# EEG_ECG.net
KiCad netlist of a schematic drawn in Altium Designer
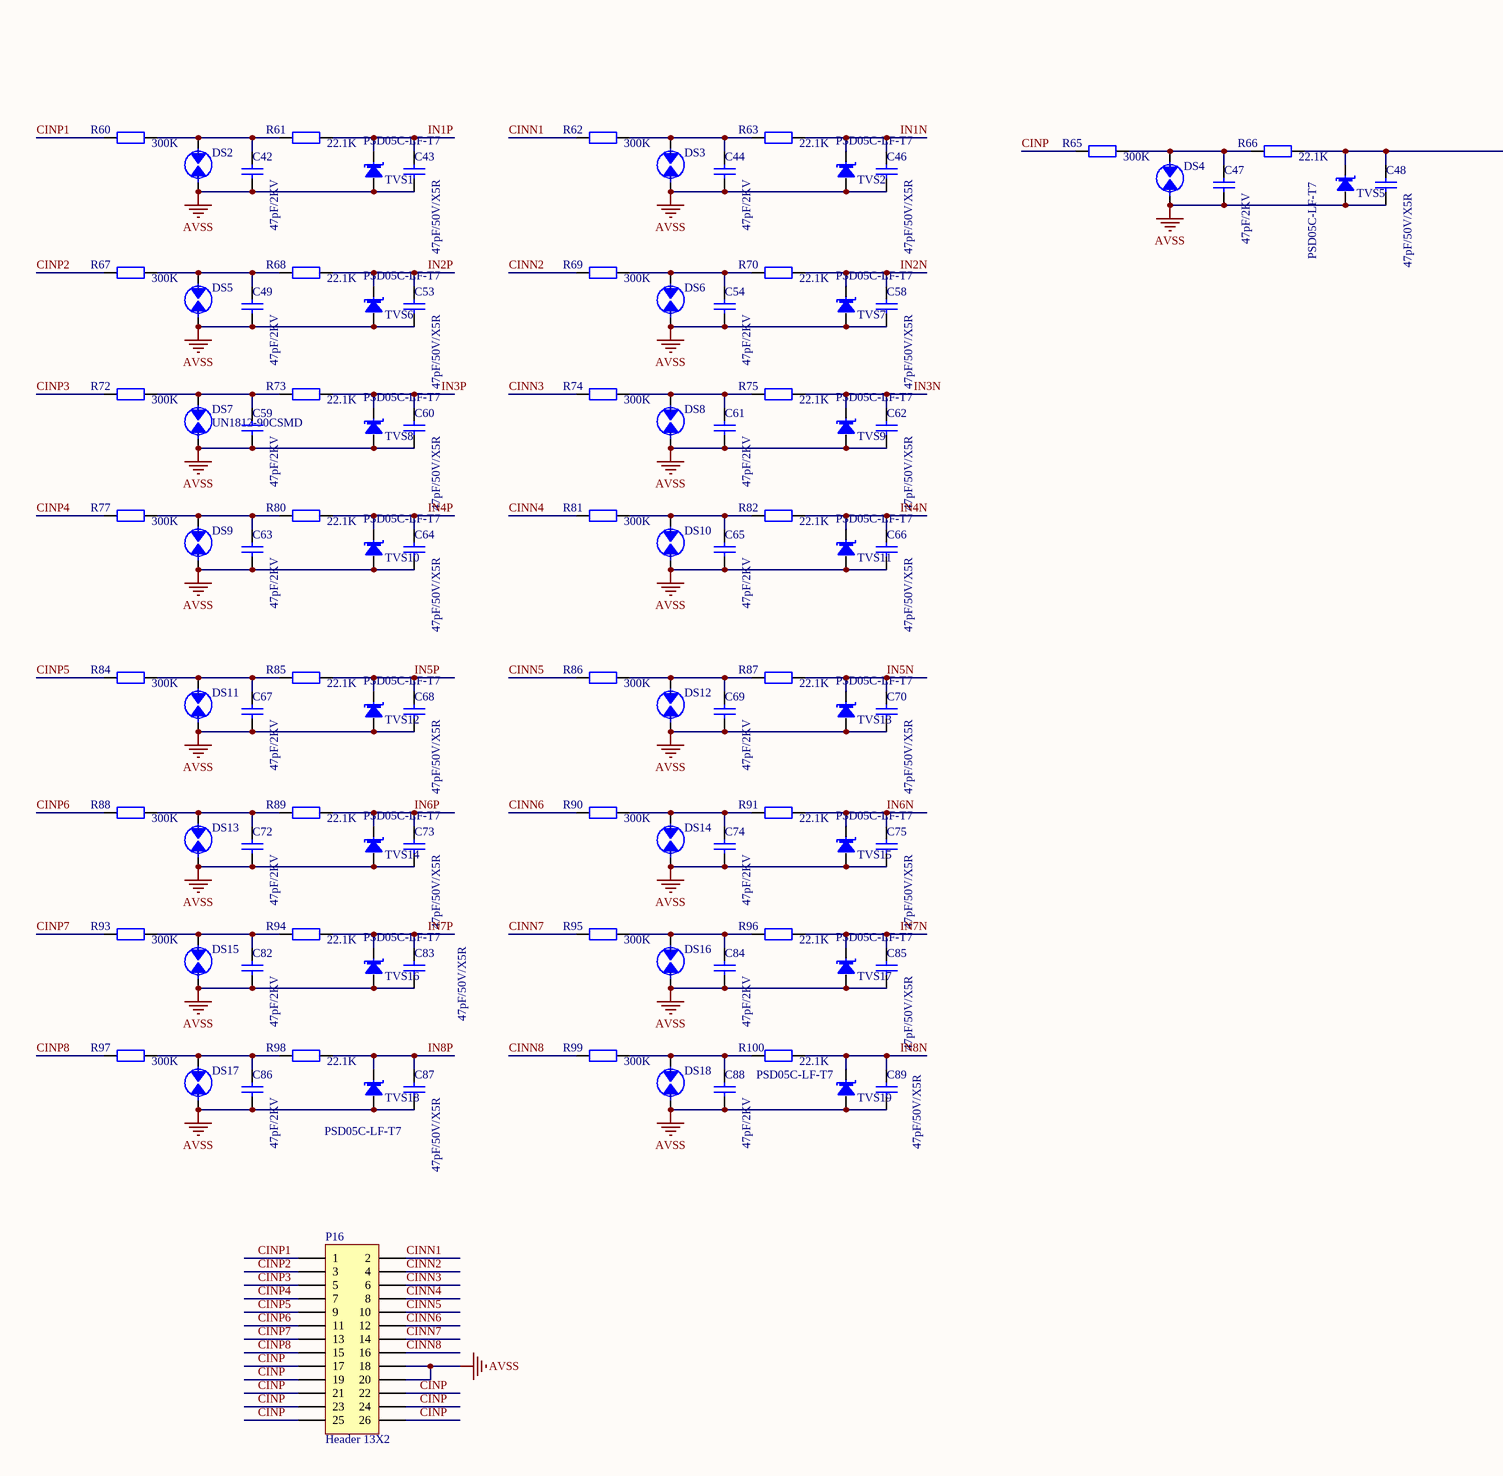
[diagram p0: EEG&ECG.SchDoc, top left]
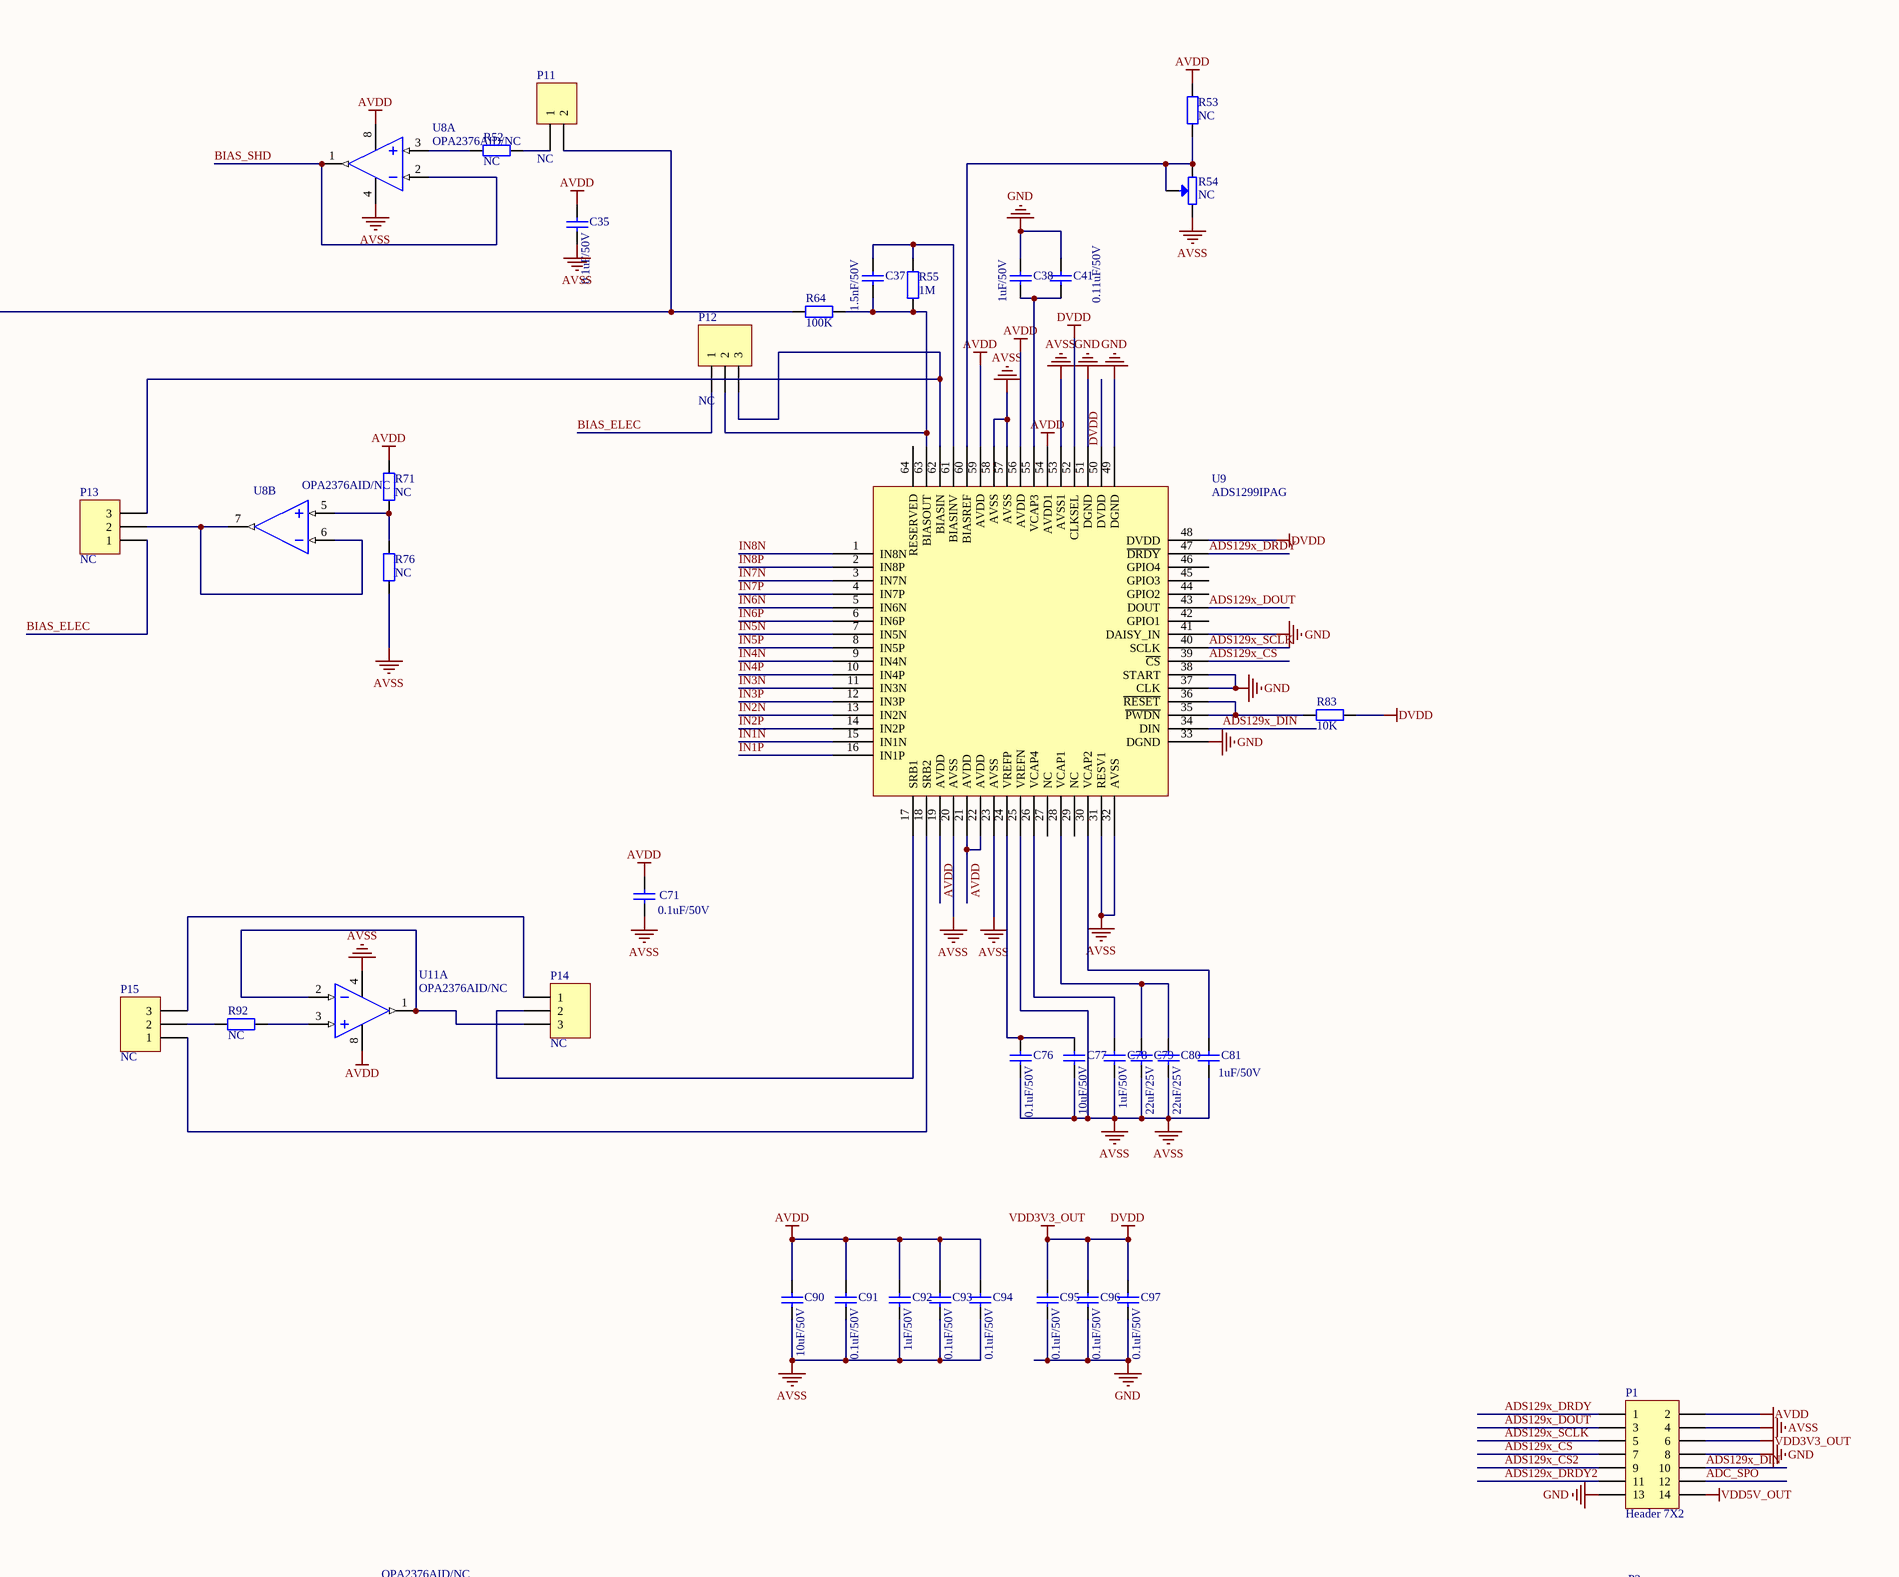
[diagram p1: EEG&ECG.SchDoc, top right]
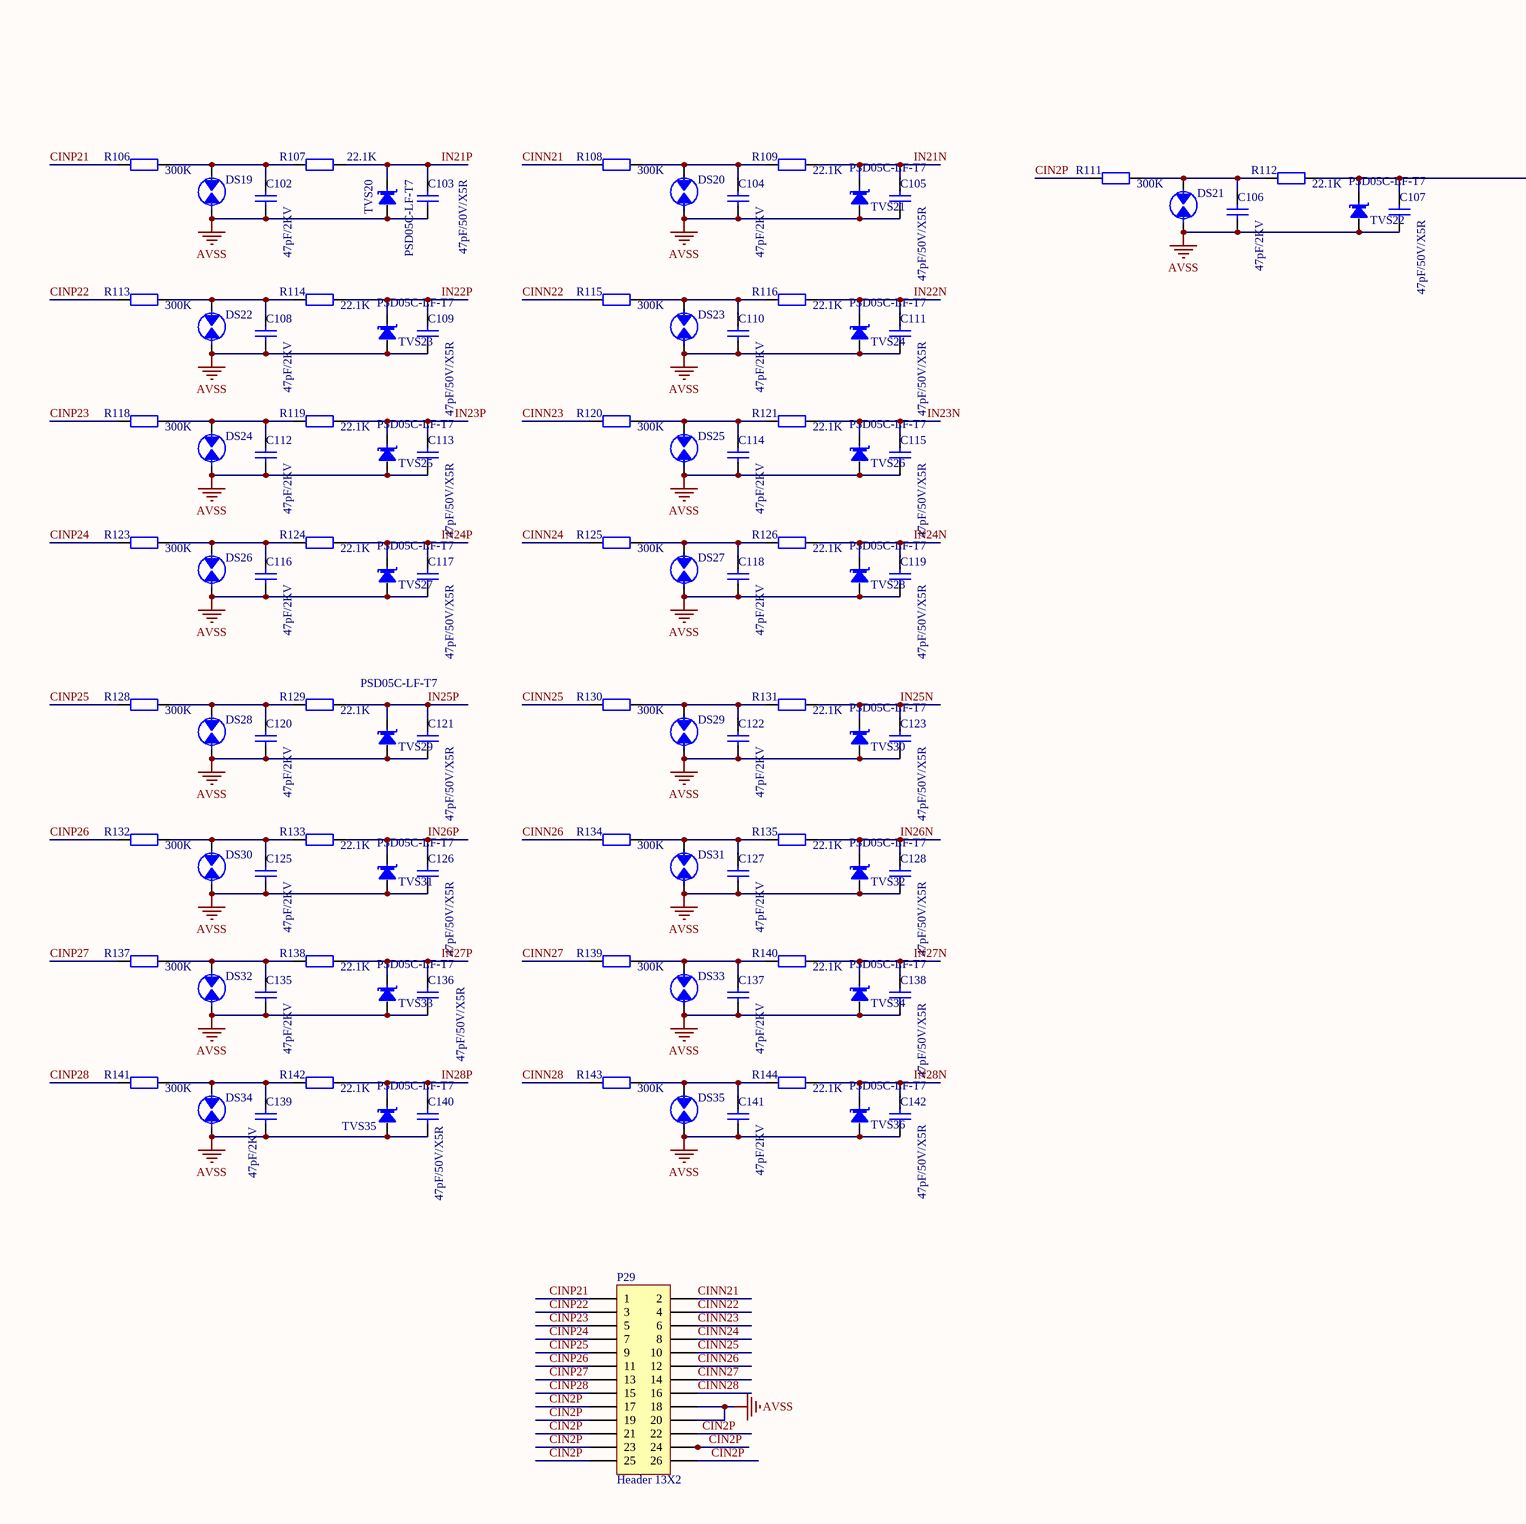
[diagram p2: EEG&ECG.SchDoc, bottom left]
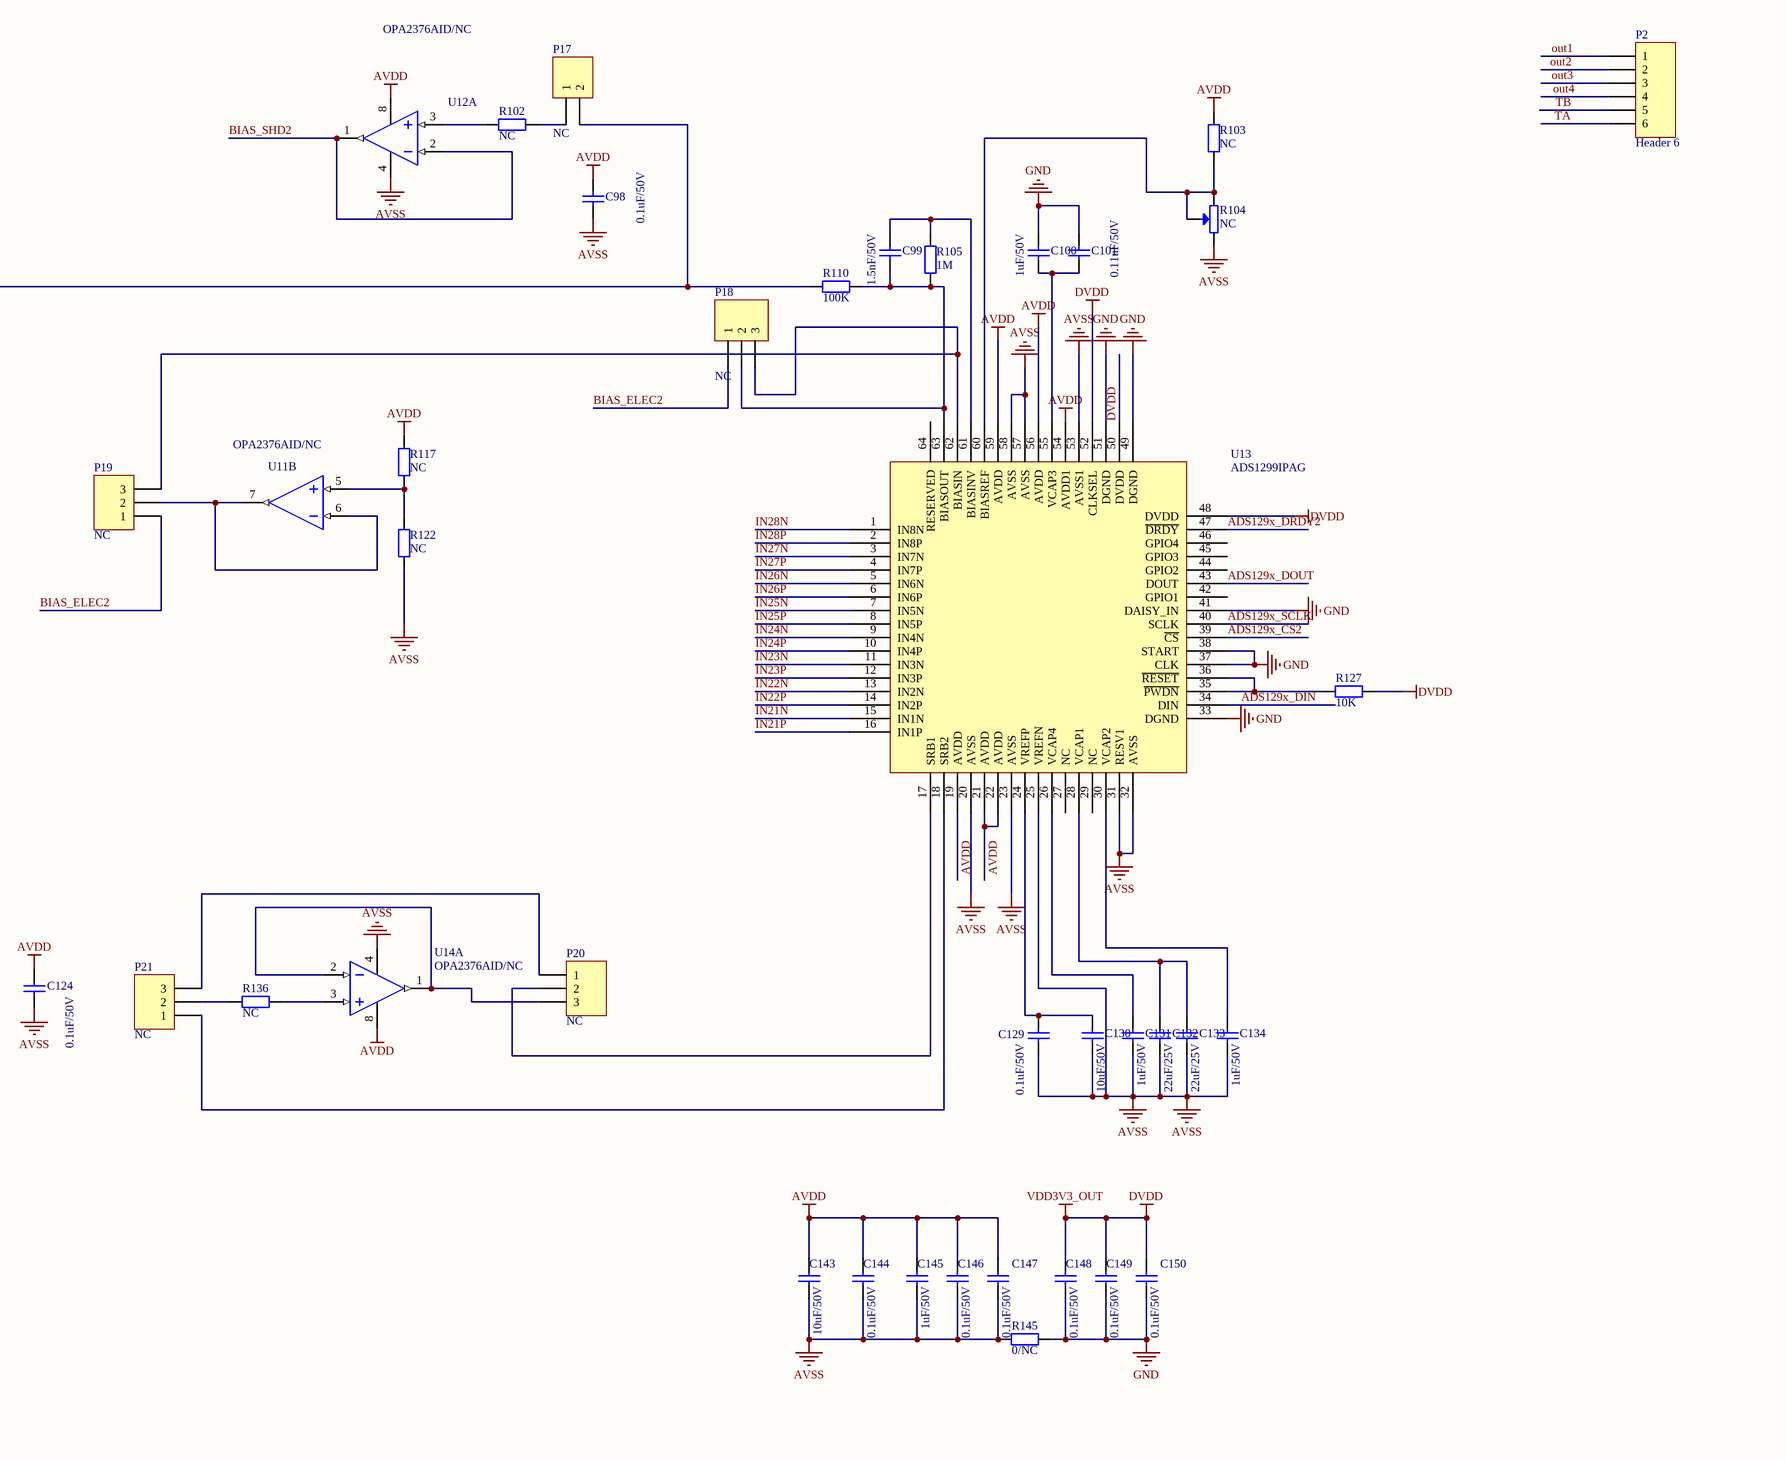
[diagram p3: EEG&ECG.SchDoc, bottom right]

(export (version "E")
  (design (tool "Eeschema 10.0.6"))
  (components
    (comp (ref "C35")
      (value "0.1uF/50V")
      (footprint "SMD-0603C")
      (description "贴片电容 20%")
      (libsource (lib "XiaoyI") (part "CAP4"))
    )
    (comp (ref "C37")
      (value "1.5nF/50V")
      (footprint "SMD-0603C")
      (description "贴片电容 20%")
      (libsource (lib "XiaoyI") (part "CAP4"))
    )
    (comp (ref "C38")
      (value "1uF/50V")
      (footprint "SMD-0603C")
      (description "贴片电容 20%")
      (libsource (lib "XiaoyI") (part "CAP4"))
    )
    (comp (ref "C41")
      (value "0.11uF/50V")
      (footprint "SMD-0603C")
      (description "贴片电容 20%")
      (libsource (lib "XiaoyI") (part "CAP4"))
    )
    (comp (ref "C42")
      (value "47pF/2KV")
      (footprint "1206c")
      (description "贴片电容 10%")
      (libsource (lib "XiaoyI") (part "CAP4"))
    )
    (comp (ref "C43")
      (value "47pF/50V/X5R")
      (footprint "SMD-0603C")
      (description "贴片电容 10%")
      (libsource (lib "XiaoyI") (part "CAP4"))
    )
    (comp (ref "C44")
      (value "47pF/2KV")
      (footprint "1206c")
      (description "贴片电容 10%")
      (libsource (lib "XiaoyI") (part "CAP4"))
    )
    (comp (ref "C46")
      (value "47pF/50V/X5R")
      (footprint "SMD-0603C")
      (description "贴片电容 10%")
      (libsource (lib "XiaoyI") (part "CAP4"))
    )
    (comp (ref "C47")
      (value "47pF/2KV")
      (footprint "1206c")
      (description "贴片电容 10%")
      (libsource (lib "XiaoyI") (part "CAP4"))
    )
    (comp (ref "C48")
      (value "47pF/50V/X5R")
      (footprint "SMD-0603C")
      (description "贴片电容 10%")
      (libsource (lib "XiaoyI") (part "CAP4"))
    )
    (comp (ref "C49")
      (value "47pF/2KV")
      (footprint "1206c")
      (description "贴片电容 10%")
      (libsource (lib "XiaoyI") (part "CAP4"))
    )
    (comp (ref "C53")
      (value "47pF/50V/X5R")
      (footprint "SMD-0603C")
      (description "贴片电容 10%")
      (libsource (lib "XiaoyI") (part "CAP4"))
    )
    (comp (ref "C54")
      (value "47pF/2KV")
      (footprint "1206c")
      (description "贴片电容 10%")
      (libsource (lib "XiaoyI") (part "CAP4"))
    )
    (comp (ref "C58")
      (value "47pF/50V/X5R")
      (footprint "SMD-0603C")
      (description "贴片电容 10%")
      (libsource (lib "XiaoyI") (part "CAP4"))
    )
    (comp (ref "C59")
      (value "47pF/2KV")
      (footprint "1206c")
      (description "贴片电容 10%")
      (libsource (lib "XiaoyI") (part "CAP4"))
    )
    (comp (ref "C60")
      (value "47pF/50V/X5R")
      (footprint "SMD-0603C")
      (description "贴片电容 10%")
      (libsource (lib "XiaoyI") (part "CAP4"))
    )
    (comp (ref "C61")
      (value "47pF/2KV")
      (footprint "1206c")
      (description "贴片电容 10%")
      (libsource (lib "XiaoyI") (part "CAP4"))
    )
    (comp (ref "C62")
      (value "47pF/50V/X5R")
      (footprint "SMD-0603C")
      (description "贴片电容 10%")
      (libsource (lib "XiaoyI") (part "CAP4"))
    )
    (comp (ref "C63")
      (value "47pF/2KV")
      (footprint "1206c")
      (description "贴片电容 10%")
      (libsource (lib "XiaoyI") (part "CAP4"))
    )
    (comp (ref "C64")
      (value "47pF/50V/X5R")
      (footprint "SMD-0603C")
      (description "贴片电容 10%")
      (libsource (lib "XiaoyI") (part "CAP4"))
    )
    (comp (ref "C65")
      (value "47pF/2KV")
      (footprint "1206c")
      (description "贴片电容 10%")
      (libsource (lib "XiaoyI") (part "CAP4"))
    )
    (comp (ref "C66")
      (value "47pF/50V/X5R")
      (footprint "SMD-0603C")
      (description "贴片电容 10%")
      (libsource (lib "XiaoyI") (part "CAP4"))
    )
    (comp (ref "C67")
      (value "47pF/2KV")
      (footprint "1206c")
      (description "贴片电容 10%")
      (libsource (lib "XiaoyI") (part "CAP4"))
    )
    (comp (ref "C68")
      (value "47pF/50V/X5R")
      (footprint "SMD-0603C")
      (description "贴片电容 10%")
      (libsource (lib "XiaoyI") (part "CAP4"))
    )
    (comp (ref "C69")
      (value "47pF/2KV")
      (footprint "1206c")
      (description "贴片电容 10%")
      (libsource (lib "XiaoyI") (part "CAP4"))
    )
    (comp (ref "C70")
      (value "47pF/50V/X5R")
      (footprint "SMD-0603C")
      (description "贴片电容 10%")
      (libsource (lib "XiaoyI") (part "CAP4"))
    )
    (comp (ref "C71")
      (value "0.1uF/50V")
      (footprint "SMD-0603C")
      (description "贴片电容 20%")
      (libsource (lib "XiaoyI") (part "CAP4"))
    )
    (comp (ref "C72")
      (value "47pF/2KV")
      (footprint "1206c")
      (description "贴片电容 10%")
      (libsource (lib "XiaoyI") (part "CAP4"))
    )
    (comp (ref "C73")
      (value "47pF/50V/X5R")
      (footprint "SMD-0603C")
      (description "贴片电容 10%")
      (libsource (lib "XiaoyI") (part "CAP4"))
    )
    (comp (ref "C74")
      (value "47pF/2KV")
      (footprint "1206c")
      (description "贴片电容 10%")
      (libsource (lib "XiaoyI") (part "CAP4"))
    )
    (comp (ref "C75")
      (value "47pF/50V/X5R")
      (footprint "SMD-0603C")
      (description "贴片电容 10%")
      (libsource (lib "XiaoyI") (part "CAP4"))
    )
    (comp (ref "C76")
      (value "0.1uF/50V")
      (footprint "SMD-0603C")
      (description "贴片电容 20%")
      (libsource (lib "XiaoyI") (part "CAP4"))
    )
    (comp (ref "C77")
      (value "10uF/50V")
      (footprint "SMD-0805C")
      (description "贴片电容 20%")
      (libsource (lib "XiaoyI") (part "CAP4"))
    )
    (comp (ref "C78")
      (value "1uF/50V")
      (footprint "SMD-0603C")
      (description "贴片电容 20%")
      (libsource (lib "XiaoyI") (part "CAP4"))
    )
    (comp (ref "C79")
      (value "22uF/25V")
      (footprint "SMD-0805C")
      (description "贴片电容 20%")
      (libsource (lib "XiaoyI") (part "CAP4"))
    )
    (comp (ref "C80")
      (value "22uF/25V")
      (footprint "SMD-0805C")
      (description "贴片电容 20%")
      (libsource (lib "XiaoyI") (part "CAP4"))
    )
    (comp (ref "C81")
      (value "1uF/50V")
      (footprint "SMD-0603C")
      (description "贴片电容 20%")
      (libsource (lib "XiaoyI") (part "CAP4"))
    )
    (comp (ref "C82")
      (value "47pF/2KV")
      (footprint "1206c")
      (description "贴片电容 10%")
      (libsource (lib "XiaoyI") (part "CAP4"))
    )
    (comp (ref "C83")
      (value "47pF/50V/X5R")
      (footprint "SMD-0603C")
      (description "贴片电容 10%")
      (libsource (lib "XiaoyI") (part "CAP4"))
    )
    (comp (ref "C84")
      (value "47pF/2KV")
      (footprint "1206c")
      (description "贴片电容 10%")
      (libsource (lib "XiaoyI") (part "CAP4"))
    )
    (comp (ref "C85")
      (value "47pF/50V/X5R")
      (footprint "SMD-0603C")
      (description "贴片电容 10%")
      (libsource (lib "XiaoyI") (part "CAP4"))
    )
    (comp (ref "C86")
      (value "47pF/2KV")
      (footprint "1206c")
      (description "贴片电容 10%")
      (libsource (lib "XiaoyI") (part "CAP4"))
    )
    (comp (ref "C87")
      (value "47pF/50V/X5R")
      (footprint "SMD-0603C")
      (description "贴片电容 10%")
      (libsource (lib "XiaoyI") (part "CAP4"))
    )
    (comp (ref "C88")
      (value "47pF/2KV")
      (footprint "1206c")
      (description "贴片电容 10%")
      (libsource (lib "XiaoyI") (part "CAP4"))
    )
    (comp (ref "C89")
      (value "47pF/50V/X5R")
      (footprint "SMD-0603C")
      (description "贴片电容 10%")
      (libsource (lib "XiaoyI") (part "CAP4"))
    )
    (comp (ref "C90")
      (value "10uF/50V")
      (footprint "SMD-0805C")
      (description "贴片电容 20%")
      (libsource (lib "XiaoyI") (part "CAP4"))
    )
    (comp (ref "C91")
      (value "0.1uF/50V")
      (footprint "SMD-0603C")
      (description "贴片电容 20%")
      (libsource (lib "XiaoyI") (part "CAP4"))
    )
    (comp (ref "C92")
      (value "1uF/50V")
      (footprint "SMD-0603C")
      (description "贴片电容 20%")
      (libsource (lib "XiaoyI") (part "CAP4"))
    )
    (comp (ref "C93")
      (value "0.1uF/50V")
      (footprint "SMD-0603C")
      (description "贴片电容 20%")
      (libsource (lib "XiaoyI") (part "CAP4"))
    )
    (comp (ref "C94")
      (value "0.1uF/50V")
      (footprint "SMD-0603C")
      (description "贴片电容 20%")
      (libsource (lib "XiaoyI") (part "CAP4"))
    )
    (comp (ref "C95")
      (value "0.1uF/50V")
      (footprint "SMD-0603C")
      (description "贴片电容 20%")
      (libsource (lib "XiaoyI") (part "CAP4"))
    )
    (comp (ref "C96")
      (value "0.1uF/50V")
      (footprint "SMD-0603C")
      (description "贴片电容 20%")
      (libsource (lib "XiaoyI") (part "CAP4"))
    )
    (comp (ref "C97")
      (value "0.1uF/50V")
      (footprint "SMD-0603C")
      (description "贴片电容 20%")
      (libsource (lib "XiaoyI") (part "CAP4"))
    )
    (comp (ref "C98")
      (value "0.1uF/50V")
      (footprint "SMD-0603C")
      (description "贴片电容 20%")
      (libsource (lib "XiaoyI") (part "CAP4"))
    )
    (comp (ref "C99")
      (value "1.5nF/50V")
      (footprint "SMD-0603C")
      (description "贴片电容 20%")
      (libsource (lib "XiaoyI") (part "CAP4"))
    )
    (comp (ref "C100")
      (value "1uF/50V")
      (footprint "SMD-0603C")
      (description "贴片电容 20%")
      (libsource (lib "XiaoyI") (part "CAP4"))
    )
    (comp (ref "C101")
      (value "0.11uF/50V")
      (footprint "SMD-0603C")
      (description "贴片电容 20%")
      (libsource (lib "XiaoyI") (part "CAP4"))
    )
    (comp (ref "C102")
      (value "47pF/2KV")
      (footprint "1206c")
      (description "贴片电容 10%")
      (libsource (lib "XiaoyI") (part "CAP4"))
    )
    (comp (ref "C103")
      (value "47pF/50V/X5R")
      (footprint "SMD-0603C")
      (description "贴片电容 10%")
      (libsource (lib "XiaoyI") (part "CAP4"))
    )
    (comp (ref "C104")
      (value "47pF/2KV")
      (footprint "1206c")
      (description "贴片电容 10%")
      (libsource (lib "XiaoyI") (part "CAP4"))
    )
    (comp (ref "C105")
      (value "47pF/50V/X5R")
      (footprint "SMD-0603C")
      (description "贴片电容 10%")
      (libsource (lib "XiaoyI") (part "CAP4"))
    )
    (comp (ref "C106")
      (value "47pF/2KV")
      (footprint "1206c")
      (description "贴片电容 10%")
      (libsource (lib "XiaoyI") (part "CAP4"))
    )
    (comp (ref "C107")
      (value "47pF/50V/X5R")
      (footprint "SMD-0603C")
      (description "贴片电容 10%")
      (libsource (lib "XiaoyI") (part "CAP4"))
    )
    (comp (ref "C108")
      (value "47pF/2KV")
      (footprint "1206c")
      (description "贴片电容 10%")
      (libsource (lib "XiaoyI") (part "CAP4"))
    )
    (comp (ref "C109")
      (value "47pF/50V/X5R")
      (footprint "SMD-0603C")
      (description "贴片电容 10%")
      (libsource (lib "XiaoyI") (part "CAP4"))
    )
    (comp (ref "C110")
      (value "47pF/2KV")
      (footprint "1206c")
      (description "贴片电容 10%")
      (libsource (lib "XiaoyI") (part "CAP4"))
    )
    (comp (ref "C111")
      (value "47pF/50V/X5R")
      (footprint "SMD-0603C")
      (description "贴片电容 10%")
      (libsource (lib "XiaoyI") (part "CAP4"))
    )
    (comp (ref "C112")
      (value "47pF/2KV")
      (footprint "1206c")
      (description "贴片电容 10%")
      (libsource (lib "XiaoyI") (part "CAP4"))
    )
    (comp (ref "C113")
      (value "47pF/50V/X5R")
      (footprint "SMD-0603C")
      (description "贴片电容 10%")
      (libsource (lib "XiaoyI") (part "CAP4"))
    )
    (comp (ref "C114")
      (value "47pF/2KV")
      (footprint "1206c")
      (description "贴片电容 10%")
      (libsource (lib "XiaoyI") (part "CAP4"))
    )
    (comp (ref "C115")
      (value "47pF/50V/X5R")
      (footprint "SMD-0603C")
      (description "贴片电容 10%")
      (libsource (lib "XiaoyI") (part "CAP4"))
    )
    (comp (ref "C116")
      (value "47pF/2KV")
      (footprint "1206c")
      (description "贴片电容 10%")
      (libsource (lib "XiaoyI") (part "CAP4"))
    )
    (comp (ref "C117")
      (value "47pF/50V/X5R")
      (footprint "SMD-0603C")
      (description "贴片电容 10%")
      (libsource (lib "XiaoyI") (part "CAP4"))
    )
    (comp (ref "C118")
      (value "47pF/2KV")
      (footprint "1206c")
      (description "贴片电容 10%")
      (libsource (lib "XiaoyI") (part "CAP4"))
    )
    (comp (ref "C119")
      (value "47pF/50V/X5R")
      (footprint "SMD-0603C")
      (description "贴片电容 10%")
      (libsource (lib "XiaoyI") (part "CAP4"))
    )
    (comp (ref "C120")
      (value "47pF/2KV")
      (footprint "1206c")
      (description "贴片电容 10%")
      (libsource (lib "XiaoyI") (part "CAP4"))
    )
    (comp (ref "C121")
      (value "47pF/50V/X5R")
      (footprint "SMD-0603C")
      (description "贴片电容 10%")
      (libsource (lib "XiaoyI") (part "CAP4"))
    )
    (comp (ref "C122")
      (value "47pF/2KV")
      (footprint "1206c")
      (description "贴片电容 10%")
      (libsource (lib "XiaoyI") (part "CAP4"))
    )
    (comp (ref "C123")
      (value "47pF/50V/X5R")
      (footprint "SMD-0603C")
      (description "贴片电容 10%")
      (libsource (lib "XiaoyI") (part "CAP4"))
    )
    (comp (ref "C124")
      (value "0.1uF/50V")
      (footprint "SMD-0603C")
      (description "贴片电容 20%")
      (libsource (lib "XiaoyI") (part "CAP4"))
    )
    (comp (ref "C125")
      (value "47pF/2KV")
      (footprint "1206c")
      (description "贴片电容 10%")
      (libsource (lib "XiaoyI") (part "CAP4"))
    )
    (comp (ref "C126")
      (value "47pF/50V/X5R")
      (footprint "SMD-0603C")
      (description "贴片电容 10%")
      (libsource (lib "XiaoyI") (part "CAP4"))
    )
    (comp (ref "C127")
      (value "47pF/2KV")
      (footprint "1206c")
      (description "贴片电容 10%")
      (libsource (lib "XiaoyI") (part "CAP4"))
    )
    (comp (ref "C128")
      (value "47pF/50V/X5R")
      (footprint "SMD-0603C")
      (description "贴片电容 10%")
      (libsource (lib "XiaoyI") (part "CAP4"))
    )
    (comp (ref "C129")
      (value "0.1uF/50V")
      (footprint "SMD-0603C")
      (description "贴片电容 20%")
      (libsource (lib "XiaoyI") (part "CAP4"))
    )
    (comp (ref "C130")
      (value "10uF/50V")
      (footprint "SMD-0805C")
      (description "贴片电容 20%")
      (libsource (lib "XiaoyI") (part "CAP4"))
    )
    (comp (ref "C131")
      (value "1uF/50V")
      (footprint "SMD-0603C")
      (description "贴片电容 20%")
      (libsource (lib "XiaoyI") (part "CAP4"))
    )
    (comp (ref "C132")
      (value "22uF/25V")
      (footprint "SMD-0805C")
      (description "贴片电容 20%")
      (libsource (lib "XiaoyI") (part "CAP4"))
    )
    (comp (ref "C133")
      (value "22uF/25V")
      (footprint "SMD-0805C")
      (description "贴片电容 20%")
      (libsource (lib "XiaoyI") (part "CAP4"))
    )
    (comp (ref "C134")
      (value "1uF/50V")
      (footprint "SMD-0603C")
      (description "贴片电容 20%")
      (libsource (lib "XiaoyI") (part "CAP4"))
    )
    (comp (ref "C135")
      (value "47pF/2KV")
      (footprint "1206c")
      (description "贴片电容 10%")
      (libsource (lib "XiaoyI") (part "CAP4"))
    )
    (comp (ref "C136")
      (value "47pF/50V/X5R")
      (footprint "SMD-0603C")
      (description "贴片电容 10%")
      (libsource (lib "XiaoyI") (part "CAP4"))
    )
    (comp (ref "C137")
      (value "47pF/2KV")
      (footprint "1206c")
      (description "贴片电容 10%")
      (libsource (lib "XiaoyI") (part "CAP4"))
    )
    (comp (ref "C138")
      (value "47pF/50V/X5R")
      (footprint "SMD-0603C")
      (description "贴片电容 10%")
      (libsource (lib "XiaoyI") (part "CAP4"))
    )
    (comp (ref "C139")
      (value "47pF/2KV")
      (footprint "1206c")
      (description "贴片电容 10%")
      (libsource (lib "XiaoyI") (part "CAP4"))
    )
    (comp (ref "C140")
      (value "47pF/50V/X5R")
      (footprint "SMD-0603C")
      (description "贴片电容 10%")
      (libsource (lib "XiaoyI") (part "CAP4"))
    )
    (comp (ref "C141")
      (value "47pF/2KV")
      (footprint "1206c")
      (description "贴片电容 10%")
      (libsource (lib "XiaoyI") (part "CAP4"))
    )
    (comp (ref "C142")
      (value "47pF/50V/X5R")
      (footprint "SMD-0603C")
      (description "贴片电容 10%")
      (libsource (lib "XiaoyI") (part "CAP4"))
    )
    (comp (ref "C143")
      (value "10uF/50V")
      (footprint "SMD-0805C")
      (description "贴片电容 20%")
      (libsource (lib "XiaoyI") (part "CAP4"))
    )
    (comp (ref "C144")
      (value "0.1uF/50V")
      (footprint "SMD-0603C")
      (description "贴片电容 20%")
      (libsource (lib "XiaoyI") (part "CAP4"))
    )
    (comp (ref "C145")
      (value "1uF/50V")
      (footprint "SMD-0603C")
      (description "贴片电容 20%")
      (libsource (lib "XiaoyI") (part "CAP4"))
    )
    (comp (ref "C146")
      (value "0.1uF/50V")
      (footprint "SMD-0603C")
      (description "贴片电容 20%")
      (libsource (lib "XiaoyI") (part "CAP4"))
    )
    (comp (ref "C147")
      (value "0.1uF/50V")
      (footprint "SMD-0603C")
      (description "贴片电容 20%")
      (libsource (lib "XiaoyI") (part "CAP4"))
    )
    (comp (ref "C148")
      (value "0.1uF/50V")
      (footprint "SMD-0603C")
      (description "贴片电容 20%")
      (libsource (lib "XiaoyI") (part "CAP4"))
    )
    (comp (ref "C149")
      (value "0.1uF/50V")
      (footprint "SMD-0603C")
      (description "贴片电容 20%")
      (libsource (lib "XiaoyI") (part "CAP4"))
    )
    (comp (ref "C150")
      (value "0.1uF/50V")
      (footprint "SMD-0603C")
      (description "贴片电容 20%")
      (libsource (lib "XiaoyI") (part "CAP4"))
    )
    (comp (ref "DS2")
      (value "UN1812-90CSMD")
      (footprint "SMD-1812")
      (description "气体放电管 90V")
      (libsource (lib "ABB") (part "DISCHARE-1"))
    )
    (comp (ref "DS3")
      (value "UN1812-90CSMD")
      (footprint "SMD-1812")
      (description "气体放电管 90V")
      (libsource (lib "ABB") (part "DISCHARE-1"))
    )
    (comp (ref "DS4")
      (value "UN1812-90CSMD")
      (footprint "SMD-1812")
      (description "气体放电管 90V")
      (libsource (lib "ABB") (part "DISCHARE-1"))
    )
    (comp (ref "DS5")
      (value "UN1812-90CSMD")
      (footprint "SMD-1812")
      (description "气体放电管 90V")
      (libsource (lib "ABB") (part "DISCHARE-1"))
    )
    (comp (ref "DS6")
      (value "UN1812-90CSMD")
      (footprint "SMD-1812")
      (description "气体放电管 90V")
      (libsource (lib "ABB") (part "DISCHARE-1"))
    )
    (comp (ref "DS7")
      (value "UN1812-90CSMD")
      (footprint "SMD-1812")
      (description "气体放电管 90V")
      (libsource (lib "ABB") (part "DISCHARE-1"))
    )
    (comp (ref "DS8")
      (value "UN1812-90CSMD")
      (footprint "SMD-1812")
      (description "气体放电管 90V")
      (libsource (lib "ABB") (part "DISCHARE-1"))
    )
    (comp (ref "DS9")
      (value "UN1812-90CSMD")
      (footprint "SMD-1812")
      (description "气体放电管 90V")
      (libsource (lib "ABB") (part "DISCHARE-1"))
    )
    (comp (ref "DS10")
      (value "UN1812-90CSMD")
      (footprint "SMD-1812")
      (description "气体放电管 90V")
      (libsource (lib "ABB") (part "DISCHARE-1"))
    )
    (comp (ref "DS11")
      (value "UN1812-90CSMD")
      (footprint "SMD-1812")
      (description "气体放电管 90V")
      (libsource (lib "ABB") (part "DISCHARE-1"))
    )
    (comp (ref "DS12")
      (value "UN1812-90CSMD")
      (footprint "SMD-1812")
      (description "气体放电管 90V")
      (libsource (lib "ABB") (part "DISCHARE-1"))
    )
    (comp (ref "DS13")
      (value "UN1812-90CSMD")
      (footprint "SMD-1812")
      (description "气体放电管 90V")
      (libsource (lib "ABB") (part "DISCHARE-1"))
    )
    (comp (ref "DS14")
      (value "UN1812-90CSMD")
      (footprint "SMD-1812")
      (description "气体放电管 90V")
      (libsource (lib "ABB") (part "DISCHARE-1"))
    )
    (comp (ref "DS15")
      (value "UN1812-90CSMD")
      (footprint "SMD-1812")
      (description "气体放电管 90V")
      (libsource (lib "ABB") (part "DISCHARE-1"))
    )
    (comp (ref "DS16")
      (value "UN1812-90CSMD")
      (footprint "SMD-1812")
      (description "气体放电管 90V")
      (libsource (lib "ABB") (part "DISCHARE-1"))
    )
    (comp (ref "DS17")
      (value "UN1812-90CSMD")
      (footprint "SMD-1812")
      (description "气体放电管 90V")
      (libsource (lib "ABB") (part "DISCHARE-1"))
    )
    (comp (ref "DS18")
      (value "UN1812-90CSMD")
      (footprint "SMD-1812")
      (description "气体放电管 90V")
      (libsource (lib "ABB") (part "DISCHARE-1"))
    )
    (comp (ref "DS19")
      (value "UN1812-90CSMD")
      (footprint "SMD-1812")
      (description "气体放电管 90V")
      (libsource (lib "ABB") (part "DISCHARE-1"))
    )
    (comp (ref "DS20")
      (value "UN1812-90CSMD")
      (footprint "SMD-1812")
      (description "气体放电管 90V")
      (libsource (lib "ABB") (part "DISCHARE-1"))
    )
    (comp (ref "DS21")
      (value "UN1812-90CSMD")
      (footprint "SMD-1812")
      (description "气体放电管 90V")
      (libsource (lib "ABB") (part "DISCHARE-1"))
    )
    (comp (ref "DS22")
      (value "UN1812-90CSMD")
      (footprint "SMD-1812")
      (description "气体放电管 90V")
      (libsource (lib "ABB") (part "DISCHARE-1"))
    )
    (comp (ref "DS23")
      (value "UN1812-90CSMD")
      (footprint "SMD-1812")
      (description "气体放电管 90V")
      (libsource (lib "ABB") (part "DISCHARE-1"))
    )
    (comp (ref "DS24")
      (value "UN1812-90CSMD")
      (footprint "SMD-1812")
      (description "气体放电管 90V")
      (libsource (lib "ABB") (part "DISCHARE-1"))
    )
    (comp (ref "DS25")
      (value "UN1812-90CSMD")
      (footprint "SMD-1812")
      (description "气体放电管 90V")
      (libsource (lib "ABB") (part "DISCHARE-1"))
    )
    (comp (ref "DS26")
      (value "UN1812-90CSMD")
      (footprint "SMD-1812")
      (description "气体放电管 90V")
      (libsource (lib "ABB") (part "DISCHARE-1"))
    )
    (comp (ref "DS27")
      (value "UN1812-90CSMD")
      (footprint "SMD-1812")
      (description "气体放电管 90V")
      (libsource (lib "ABB") (part "DISCHARE-1"))
    )
    (comp (ref "DS28")
      (value "UN1812-90CSMD")
      (footprint "SMD-1812")
      (description "气体放电管 90V")
      (libsource (lib "ABB") (part "DISCHARE-1"))
    )
    (comp (ref "DS29")
      (value "UN1812-90CSMD")
      (footprint "SMD-1812")
      (description "气体放电管 90V")
      (libsource (lib "ABB") (part "DISCHARE-1"))
    )
    (comp (ref "DS30")
      (value "UN1812-90CSMD")
      (footprint "SMD-1812")
      (description "气体放电管 90V")
      (libsource (lib "ABB") (part "DISCHARE-1"))
    )
    (comp (ref "DS31")
      (value "UN1812-90CSMD")
      (footprint "SMD-1812")
      (description "气体放电管 90V")
      (libsource (lib "ABB") (part "DISCHARE-1"))
    )
    (comp (ref "DS32")
      (value "UN1812-90CSMD")
      (footprint "SMD-1812")
      (description "气体放电管 90V")
      (libsource (lib "ABB") (part "DISCHARE-1"))
    )
    (comp (ref "DS33")
      (value "UN1812-90CSMD")
      (footprint "SMD-1812")
      (description "气体放电管 90V")
      (libsource (lib "ABB") (part "DISCHARE-1"))
    )
    (comp (ref "DS34")
      (value "UN1812-90CSMD")
      (footprint "SMD-1812")
      (description "气体放电管 90V")
      (libsource (lib "ABB") (part "DISCHARE-1"))
    )
    (comp (ref "DS35")
      (value "UN1812-90CSMD")
      (footprint "SMD-1812")
      (description "气体放电管 90V")
      (libsource (lib "ABB") (part "DISCHARE-1"))
    )
    (comp (ref "P1")
      (value "Header 7X2")
      (footprint "HDR2X7")
      (description "Header, 7-Pin, Dual row")
      (fields (field (name "PUBLISHER") "Altium Limited"))
      (libsource (lib "Miscellaneous Connectors") (part "Header 7X2"))
    )
    (comp (ref "P2")
      (value "Header 6")
      (footprint "HDR1X6")
      (description "Header, 6-Pin")
      (fields (field (name "PUBLISHER") "Altium Limited"))
      (libsource (lib "Miscellaneous Connectors") (part "Header 6"))
    )
    (comp (ref "P11")
      (value "NC")
      (footprint "HDR1X2")
      (description "Header, 2-Pin")
      (fields (field (name "PUBLISHER") "Altium Limited"))
      (libsource (lib "Miscellaneous Connectors") (part "Header 2"))
    )
    (comp (ref "P12")
      (value "NC")
      (footprint "HDR1X3")
      (description "Header, 3-Pin")
      (fields (field (name "PUBLISHER") "Altium Limited"))
      (libsource (lib "Miscellaneous Connectors") (part "Header 3"))
    )
    (comp (ref "P13")
      (value "NC")
      (footprint "HDR1X3")
      (description "Header, 3-Pin")
      (fields (field (name "PUBLISHER") "Altium Limited"))
      (libsource (lib "") (part "Header 3_1"))
    )
    (comp (ref "P14")
      (value "NC")
      (footprint "HDR1X3")
      (description "Header, 3-Pin")
      (fields (field (name "PUBLISHER") "Altium Limited"))
      (libsource (lib "") (part "Header 3_2"))
    )
    (comp (ref "P15")
      (value "NC")
      (footprint "HDR1X3")
      (description "Header, 3-Pin")
      (fields (field (name "PUBLISHER") "Altium Limited"))
      (libsource (lib "") (part "Header 3_1"))
    )
    (comp (ref "P16")
      (value "Header 13X2")
      (footprint "HDR2X13")
      (description "Header, 13-Pin, Dual row")
      (fields (field (name "PUBLISHER") "Altium Limited"))
      (libsource (lib "Miscellaneous Connectors") (part "Header 13X2"))
    )
    (comp (ref "P17")
      (value "NC")
      (footprint "HDR1X2")
      (description "Header, 2-Pin")
      (fields (field (name "PUBLISHER") "Altium Limited"))
      (libsource (lib "Miscellaneous Connectors") (part "Header 2"))
    )
    (comp (ref "P18")
      (value "NC")
      (footprint "HDR1X3")
      (description "Header, 3-Pin")
      (fields (field (name "PUBLISHER") "Altium Limited"))
      (libsource (lib "Miscellaneous Connectors") (part "Header 3"))
    )
    (comp (ref "P19")
      (value "NC")
      (footprint "HDR1X3")
      (description "Header, 3-Pin")
      (fields (field (name "PUBLISHER") "Altium Limited"))
      (libsource (lib "") (part "Header 3_1"))
    )
    (comp (ref "P20")
      (value "NC")
      (footprint "HDR1X3")
      (description "Header, 3-Pin")
      (fields (field (name "PUBLISHER") "Altium Limited"))
      (libsource (lib "") (part "Header 3_2"))
    )
    (comp (ref "P21")
      (value "NC")
      (footprint "HDR1X3")
      (description "Header, 3-Pin")
      (fields (field (name "PUBLISHER") "Altium Limited"))
      (libsource (lib "") (part "Header 3_1"))
    )
    (comp (ref "P29")
      (value "Header 13X2")
      (footprint "HDR2X13")
      (description "Header, 13-Pin, Dual row")
      (fields (field (name "PUBLISHER") "Altium Limited"))
      (libsource (lib "Miscellaneous Connectors") (part "Header 13X2"))
    )
    (comp (ref "R52")
      (value "NC")
      (footprint "SMD-0603")
      (description "贴片电阻 5%")
      (libsource (lib "XiaoyI") (part "RES2"))
    )
    (comp (ref "R53")
      (value "NC")
      (footprint "SMD-0603")
      (description "贴片电阻 5%")
      (libsource (lib "") (part "RES2_1"))
    )
    (comp (ref "R54")
      (value "NC")
      (footprint "VR-05")
      (description "可调电阻")
      (libsource (lib "ABB") (part "RES4"))
    )
    (comp (ref "R55")
      (value "1M")
      (footprint "SMD-0603")
      (description "贴片电阻 5%")
      (libsource (lib "") (part "RES2_1"))
    )
    (comp (ref "R60")
      (value "300K")
      (footprint "SMD-0603")
      (description "贴片电阻 1%")
      (libsource (lib "ABB") (part "RES0"))
    )
    (comp (ref "R61")
      (value "22.1K")
      (footprint "SMD-0603")
      (description "贴片电阻 1%")
      (libsource (lib "ABB") (part "RES0"))
    )
    (comp (ref "R62")
      (value "300K")
      (footprint "SMD-0603")
      (description "贴片电阻 1%")
      (libsource (lib "ABB") (part "RES0"))
    )
    (comp (ref "R63")
      (value "22.1K")
      (footprint "SMD-0603")
      (description "贴片电阻 1%")
      (libsource (lib "ABB") (part "RES0"))
    )
    (comp (ref "R64")
      (value "100K")
      (footprint "SMD-0603")
      (description "贴片电阻 5%")
      (libsource (lib "XiaoyI") (part "RES2"))
    )
    (comp (ref "R65")
      (value "300K")
      (footprint "SMD-0603")
      (description "贴片电阻 1%")
      (libsource (lib "ABB") (part "RES0"))
    )
    (comp (ref "R66")
      (value "22.1K")
      (footprint "SMD-0603")
      (description "贴片电阻 1%")
      (libsource (lib "ABB") (part "RES0"))
    )
    (comp (ref "R67")
      (value "300K")
      (footprint "SMD-0603")
      (description "贴片电阻 1%")
      (libsource (lib "ABB") (part "RES0"))
    )
    (comp (ref "R68")
      (value "22.1K")
      (footprint "SMD-0603")
      (description "贴片电阻 1%")
      (libsource (lib "ABB") (part "RES0"))
    )
    (comp (ref "R69")
      (value "300K")
      (footprint "SMD-0603")
      (description "贴片电阻 1%")
      (libsource (lib "ABB") (part "RES0"))
    )
    (comp (ref "R70")
      (value "22.1K")
      (footprint "SMD-0603")
      (description "贴片电阻 1%")
      (libsource (lib "ABB") (part "RES0"))
    )
    (comp (ref "R71")
      (value "NC")
      (footprint "SMD-0603")
      (description "贴片电阻 5%")
      (libsource (lib "") (part "RES2_1"))
    )
    (comp (ref "R72")
      (value "300K")
      (footprint "SMD-0603")
      (description "贴片电阻 1%")
      (libsource (lib "ABB") (part "RES0"))
    )
    (comp (ref "R73")
      (value "22.1K")
      (footprint "SMD-0603")
      (description "贴片电阻 1%")
      (libsource (lib "ABB") (part "RES0"))
    )
    (comp (ref "R74")
      (value "300K")
      (footprint "SMD-0603")
      (description "贴片电阻 1%")
      (libsource (lib "ABB") (part "RES0"))
    )
    (comp (ref "R75")
      (value "22.1K")
      (footprint "SMD-0603")
      (description "贴片电阻 1%")
      (libsource (lib "ABB") (part "RES0"))
    )
    (comp (ref "R76")
      (value "NC")
      (footprint "SMD-0603")
      (description "贴片电阻 5%")
      (libsource (lib "") (part "RES2_1"))
    )
    (comp (ref "R77")
      (value "300K")
      (footprint "SMD-0603")
      (description "贴片电阻 1%")
      (libsource (lib "ABB") (part "RES0"))
    )
    (comp (ref "R80")
      (value "22.1K")
      (footprint "SMD-0603")
      (description "贴片电阻 1%")
      (libsource (lib "ABB") (part "RES0"))
    )
    (comp (ref "R81")
      (value "300K")
      (footprint "SMD-0603")
      (description "贴片电阻 1%")
      (libsource (lib "ABB") (part "RES0"))
    )
    (comp (ref "R82")
      (value "22.1K")
      (footprint "SMD-0603")
      (description "贴片电阻 1%")
      (libsource (lib "ABB") (part "RES0"))
    )
    (comp (ref "R83")
      (value "10K")
      (footprint "SMD-0603")
      (description "贴片电阻 5%")
      (libsource (lib "XiaoyI") (part "RES2"))
    )
    (comp (ref "R84")
      (value "300K")
      (footprint "SMD-0603")
      (description "贴片电阻 1%")
      (libsource (lib "ABB") (part "RES0"))
    )
    (comp (ref "R85")
      (value "22.1K")
      (footprint "SMD-0603")
      (description "贴片电阻 1%")
      (libsource (lib "ABB") (part "RES0"))
    )
    (comp (ref "R86")
      (value "300K")
      (footprint "SMD-0603")
      (description "贴片电阻 1%")
      (libsource (lib "ABB") (part "RES0"))
    )
    (comp (ref "R87")
      (value "22.1K")
      (footprint "SMD-0603")
      (description "贴片电阻 1%")
      (libsource (lib "ABB") (part "RES0"))
    )
    (comp (ref "R88")
      (value "300K")
      (footprint "SMD-0603")
      (description "贴片电阻 1%")
      (libsource (lib "ABB") (part "RES0"))
    )
    (comp (ref "R89")
      (value "22.1K")
      (footprint "SMD-0603")
      (description "贴片电阻 1%")
      (libsource (lib "ABB") (part "RES0"))
    )
    (comp (ref "R90")
      (value "300K")
      (footprint "SMD-0603")
      (description "贴片电阻 1%")
      (libsource (lib "ABB") (part "RES0"))
    )
    (comp (ref "R91")
      (value "22.1K")
      (footprint "SMD-0603")
      (description "贴片电阻 1%")
      (libsource (lib "ABB") (part "RES0"))
    )
    (comp (ref "R92")
      (value "NC")
      (footprint "SMD-0603")
      (description "贴片电阻 5%")
      (libsource (lib "") (part "RES2_2"))
    )
    (comp (ref "R93")
      (value "300K")
      (footprint "SMD-0603")
      (description "贴片电阻 1%")
      (libsource (lib "ABB") (part "RES0"))
    )
    (comp (ref "R94")
      (value "22.1K")
      (footprint "SMD-0603")
      (description "贴片电阻 1%")
      (libsource (lib "ABB") (part "RES0"))
    )
    (comp (ref "R95")
      (value "300K")
      (footprint "SMD-0603")
      (description "贴片电阻 1%")
      (libsource (lib "ABB") (part "RES0"))
    )
    (comp (ref "R96")
      (value "22.1K")
      (footprint "SMD-0603")
      (description "贴片电阻 1%")
      (libsource (lib "ABB") (part "RES0"))
    )
    (comp (ref "R97")
      (value "300K")
      (footprint "SMD-0603")
      (description "贴片电阻 1%")
      (libsource (lib "ABB") (part "RES0"))
    )
    (comp (ref "R98")
      (value "22.1K")
      (footprint "SMD-0603")
      (description "贴片电阻 1%")
      (libsource (lib "ABB") (part "RES0"))
    )
    (comp (ref "R99")
      (value "300K")
      (footprint "SMD-0603")
      (description "贴片电阻 1%")
      (libsource (lib "ABB") (part "RES0"))
    )
    (comp (ref "R100")
      (value "22.1K")
      (footprint "SMD-0603")
      (description "贴片电阻 1%")
      (libsource (lib "ABB") (part "RES0"))
    )
    (comp (ref "R102")
      (value "NC")
      (footprint "SMD-0603")
      (description "贴片电阻 5%")
      (libsource (lib "XiaoyI") (part "RES2"))
    )
    (comp (ref "R103")
      (value "NC")
      (footprint "SMD-0603")
      (description "贴片电阻 5%")
      (libsource (lib "") (part "RES2_1"))
    )
    (comp (ref "R104")
      (value "NC")
      (footprint "VR-05")
      (description "可调电阻")
      (libsource (lib "ABB") (part "RES4"))
    )
    (comp (ref "R105")
      (value "1M")
      (footprint "SMD-0603")
      (description "贴片电阻 5%")
      (libsource (lib "") (part "RES2_1"))
    )
    (comp (ref "R106")
      (value "300K")
      (footprint "SMD-0603")
      (description "贴片电阻 1%")
      (libsource (lib "ABB") (part "RES0"))
    )
    (comp (ref "R107")
      (value "22.1K")
      (footprint "SMD-0603")
      (description "贴片电阻 1%")
      (libsource (lib "ABB") (part "RES0"))
    )
    (comp (ref "R108")
      (value "300K")
      (footprint "SMD-0603")
      (description "贴片电阻 1%")
      (libsource (lib "ABB") (part "RES0"))
    )
    (comp (ref "R109")
      (value "22.1K")
      (footprint "SMD-0603")
      (description "贴片电阻 1%")
      (libsource (lib "ABB") (part "RES0"))
    )
    (comp (ref "R110")
      (value "100K")
      (footprint "SMD-0603")
      (description "贴片电阻 5%")
      (libsource (lib "XiaoyI") (part "RES2"))
    )
    (comp (ref "R111")
      (value "300K")
      (footprint "SMD-0603")
      (description "贴片电阻 1%")
      (libsource (lib "ABB") (part "RES0"))
    )
    (comp (ref "R112")
      (value "22.1K")
      (footprint "SMD-0603")
      (description "贴片电阻 1%")
      (libsource (lib "ABB") (part "RES0"))
    )
    (comp (ref "R113")
      (value "300K")
      (footprint "SMD-0603")
      (description "贴片电阻 1%")
      (libsource (lib "ABB") (part "RES0"))
    )
    (comp (ref "R114")
      (value "22.1K")
      (footprint "SMD-0603")
      (description "贴片电阻 1%")
      (libsource (lib "ABB") (part "RES0"))
    )
    (comp (ref "R115")
      (value "300K")
      (footprint "SMD-0603")
      (description "贴片电阻 1%")
      (libsource (lib "ABB") (part "RES0"))
    )
    (comp (ref "R116")
      (value "22.1K")
      (footprint "SMD-0603")
      (description "贴片电阻 1%")
      (libsource (lib "ABB") (part "RES0"))
    )
    (comp (ref "R117")
      (value "NC")
      (footprint "SMD-0603")
      (description "贴片电阻 5%")
      (libsource (lib "") (part "RES2_1"))
    )
    (comp (ref "R118")
      (value "300K")
      (footprint "SMD-0603")
      (description "贴片电阻 1%")
      (libsource (lib "ABB") (part "RES0"))
    )
    (comp (ref "R119")
      (value "22.1K")
      (footprint "SMD-0603")
      (description "贴片电阻 1%")
      (libsource (lib "ABB") (part "RES0"))
    )
    (comp (ref "R120")
      (value "300K")
      (footprint "SMD-0603")
      (description "贴片电阻 1%")
      (libsource (lib "ABB") (part "RES0"))
    )
    (comp (ref "R121")
      (value "22.1K")
      (footprint "SMD-0603")
      (description "贴片电阻 1%")
      (libsource (lib "ABB") (part "RES0"))
    )
    (comp (ref "R122")
      (value "NC")
      (footprint "SMD-0603")
      (description "贴片电阻 5%")
      (libsource (lib "") (part "RES2_1"))
    )
    (comp (ref "R123")
      (value "300K")
      (footprint "SMD-0603")
      (description "贴片电阻 1%")
      (libsource (lib "ABB") (part "RES0"))
    )
    (comp (ref "R124")
      (value "22.1K")
      (footprint "SMD-0603")
      (description "贴片电阻 1%")
      (libsource (lib "ABB") (part "RES0"))
    )
    (comp (ref "R125")
      (value "300K")
      (footprint "SMD-0603")
      (description "贴片电阻 1%")
      (libsource (lib "ABB") (part "RES0"))
    )
    (comp (ref "R126")
      (value "22.1K")
      (footprint "SMD-0603")
      (description "贴片电阻 1%")
      (libsource (lib "ABB") (part "RES0"))
    )
    (comp (ref "R127")
      (value "10K")
      (footprint "SMD-0603")
      (description "贴片电阻 5%")
      (libsource (lib "XiaoyI") (part "RES2"))
    )
    (comp (ref "R128")
      (value "300K")
      (footprint "SMD-0603")
      (description "贴片电阻 1%")
      (libsource (lib "ABB") (part "RES0"))
    )
    (comp (ref "R129")
      (value "22.1K")
      (footprint "SMD-0603")
      (description "贴片电阻 1%")
      (libsource (lib "ABB") (part "RES0"))
    )
    (comp (ref "R130")
      (value "300K")
      (footprint "SMD-0603")
      (description "贴片电阻 1%")
      (libsource (lib "ABB") (part "RES0"))
    )
    (comp (ref "R131")
      (value "22.1K")
      (footprint "SMD-0603")
      (description "贴片电阻 1%")
      (libsource (lib "ABB") (part "RES0"))
    )
    (comp (ref "R132")
      (value "300K")
      (footprint "SMD-0603")
      (description "贴片电阻 1%")
      (libsource (lib "ABB") (part "RES0"))
    )
    (comp (ref "R133")
      (value "22.1K")
      (footprint "SMD-0603")
      (description "贴片电阻 1%")
      (libsource (lib "ABB") (part "RES0"))
    )
    (comp (ref "R134")
      (value "300K")
      (footprint "SMD-0603")
      (description "贴片电阻 1%")
      (libsource (lib "ABB") (part "RES0"))
    )
    (comp (ref "R135")
      (value "22.1K")
      (footprint "SMD-0603")
      (description "贴片电阻 1%")
      (libsource (lib "ABB") (part "RES0"))
    )
    (comp (ref "R136")
      (value "NC")
      (footprint "SMD-0603")
      (description "贴片电阻 5%")
      (libsource (lib "") (part "RES2_2"))
    )
    (comp (ref "R137")
      (value "300K")
      (footprint "SMD-0603")
      (description "贴片电阻 1%")
      (libsource (lib "ABB") (part "RES0"))
    )
    (comp (ref "R138")
      (value "22.1K")
      (footprint "SMD-0603")
      (description "贴片电阻 1%")
      (libsource (lib "ABB") (part "RES0"))
    )
    (comp (ref "R139")
      (value "300K")
      (footprint "SMD-0603")
      (description "贴片电阻 1%")
      (libsource (lib "ABB") (part "RES0"))
    )
    (comp (ref "R140")
      (value "22.1K")
      (footprint "SMD-0603")
      (description "贴片电阻 1%")
      (libsource (lib "ABB") (part "RES0"))
    )
    (comp (ref "R141")
      (value "300K")
      (footprint "SMD-0603")
      (description "贴片电阻 1%")
      (libsource (lib "ABB") (part "RES0"))
    )
    (comp (ref "R142")
      (value "22.1K")
      (footprint "SMD-0603")
      (description "贴片电阻 1%")
      (libsource (lib "ABB") (part "RES0"))
    )
    (comp (ref "R143")
      (value "300K")
      (footprint "SMD-0603")
      (description "贴片电阻 1%")
      (libsource (lib "ABB") (part "RES0"))
    )
    (comp (ref "R144")
      (value "22.1K")
      (footprint "SMD-0603")
      (description "贴片电阻 1%")
      (libsource (lib "ABB") (part "RES0"))
    )
    (comp (ref "R145")
      (value "0/NC")
      (footprint "SMD-1206")
      (description "贴片电阻 5%")
      (libsource (lib "XiaoyI") (part "RES2"))
    )
    (comp (ref "TVS1")
      (value "PSD05C-LF-T7")
      (footprint "SOD-323")
      (description "单向TVS")
      (libsource (lib "XiaoyI") (part "TVS-S"))
    )
    (comp (ref "TVS2")
      (value "PSD05C-LF-T7")
      (footprint "SOD-323")
      (description "单向TVS")
      (libsource (lib "XiaoyI") (part "TVS-S"))
    )
    (comp (ref "TVS5")
      (value "PSD05C-LF-T7")
      (footprint "SOD-323")
      (description "单向TVS")
      (libsource (lib "XiaoyI") (part "TVS-S"))
    )
    (comp (ref "TVS6")
      (value "PSD05C-LF-T7")
      (footprint "SOD-323")
      (description "单向TVS")
      (libsource (lib "XiaoyI") (part "TVS-S"))
    )
    (comp (ref "TVS7")
      (value "PSD05C-LF-T7")
      (footprint "SOD-323")
      (description "单向TVS")
      (libsource (lib "XiaoyI") (part "TVS-S"))
    )
    (comp (ref "TVS8")
      (value "PSD05C-LF-T7")
      (footprint "SOD-323")
      (description "单向TVS")
      (libsource (lib "XiaoyI") (part "TVS-S"))
    )
    (comp (ref "TVS9")
      (value "PSD05C-LF-T7")
      (footprint "SOD-323")
      (description "单向TVS")
      (libsource (lib "XiaoyI") (part "TVS-S"))
    )
    (comp (ref "TVS10")
      (value "PSD05C-LF-T7")
      (footprint "SOD-323")
      (description "单向TVS")
      (libsource (lib "XiaoyI") (part "TVS-S"))
    )
    (comp (ref "TVS11")
      (value "PSD05C-LF-T7")
      (footprint "SOD-323")
      (description "单向TVS")
      (libsource (lib "XiaoyI") (part "TVS-S"))
    )
    (comp (ref "TVS12")
      (value "PSD05C-LF-T7")
      (footprint "SOD-323")
      (description "单向TVS")
      (libsource (lib "XiaoyI") (part "TVS-S"))
    )
    (comp (ref "TVS13")
      (value "PSD05C-LF-T7")
      (footprint "SOD-323")
      (description "单向TVS")
      (libsource (lib "XiaoyI") (part "TVS-S"))
    )
    (comp (ref "TVS14")
      (value "PSD05C-LF-T7")
      (footprint "SOD-323")
      (description "单向TVS")
      (libsource (lib "XiaoyI") (part "TVS-S"))
    )
    (comp (ref "TVS15")
      (value "PSD05C-LF-T7")
      (footprint "SOD-323")
      (description "单向TVS")
      (libsource (lib "XiaoyI") (part "TVS-S"))
    )
    (comp (ref "TVS16")
      (value "PSD05C-LF-T7")
      (footprint "SOD-323")
      (description "单向TVS")
      (libsource (lib "XiaoyI") (part "TVS-S"))
    )
    (comp (ref "TVS17")
      (value "PSD05C-LF-T7")
      (footprint "SOD-323")
      (description "单向TVS")
      (libsource (lib "XiaoyI") (part "TVS-S"))
    )
    (comp (ref "TVS18")
      (value "PSD05C-LF-T7")
      (footprint "SOD-323")
      (description "单向TVS")
      (libsource (lib "XiaoyI") (part "TVS-S"))
    )
    (comp (ref "TVS19")
      (value "PSD05C-LF-T7")
      (footprint "SOD-323")
      (description "单向TVS")
      (libsource (lib "XiaoyI") (part "TVS-S"))
    )
    (comp (ref "TVS20")
      (value "PSD05C-LF-T7")
      (footprint "SOD-323")
      (description "单向TVS")
      (libsource (lib "XiaoyI") (part "TVS-S"))
    )
    (comp (ref "TVS21")
      (value "PSD05C-LF-T7")
      (footprint "SOD-323")
      (description "单向TVS")
      (libsource (lib "XiaoyI") (part "TVS-S"))
    )
    (comp (ref "TVS22")
      (value "PSD05C-LF-T7")
      (footprint "SOD-323")
      (description "单向TVS")
      (libsource (lib "XiaoyI") (part "TVS-S"))
    )
    (comp (ref "TVS23")
      (value "PSD05C-LF-T7")
      (footprint "SOD-323")
      (description "单向TVS")
      (libsource (lib "XiaoyI") (part "TVS-S"))
    )
    (comp (ref "TVS24")
      (value "PSD05C-LF-T7")
      (footprint "SOD-323")
      (description "单向TVS")
      (libsource (lib "XiaoyI") (part "TVS-S"))
    )
    (comp (ref "TVS25")
      (value "PSD05C-LF-T7")
      (footprint "SOD-323")
      (description "单向TVS")
      (libsource (lib "XiaoyI") (part "TVS-S"))
    )
    (comp (ref "TVS26")
      (value "PSD05C-LF-T7")
      (footprint "SOD-323")
      (description "单向TVS")
      (libsource (lib "XiaoyI") (part "TVS-S"))
    )
    (comp (ref "TVS27")
      (value "PSD05C-LF-T7")
      (footprint "SOD-323")
      (description "单向TVS")
      (libsource (lib "XiaoyI") (part "TVS-S"))
    )
    (comp (ref "TVS28")
      (value "PSD05C-LF-T7")
      (footprint "SOD-323")
      (description "单向TVS")
      (libsource (lib "XiaoyI") (part "TVS-S"))
    )
    (comp (ref "TVS29")
      (value "PSD05C-LF-T7")
      (footprint "SOD-323")
      (description "单向TVS")
      (libsource (lib "XiaoyI") (part "TVS-S"))
    )
    (comp (ref "TVS30")
      (value "PSD05C-LF-T7")
      (footprint "SOD-323")
      (description "单向TVS")
      (libsource (lib "XiaoyI") (part "TVS-S"))
    )
    (comp (ref "TVS31")
      (value "PSD05C-LF-T7")
      (footprint "SOD-323")
      (description "单向TVS")
      (libsource (lib "XiaoyI") (part "TVS-S"))
    )
    (comp (ref "TVS32")
      (value "PSD05C-LF-T7")
      (footprint "SOD-323")
      (description "单向TVS")
      (libsource (lib "XiaoyI") (part "TVS-S"))
    )
    (comp (ref "TVS33")
      (value "PSD05C-LF-T7")
      (footprint "SOD-323")
      (description "单向TVS")
      (libsource (lib "XiaoyI") (part "TVS-S"))
    )
    (comp (ref "TVS34")
      (value "PSD05C-LF-T7")
      (footprint "SOD-323")
      (description "单向TVS")
      (libsource (lib "XiaoyI") (part "TVS-S"))
    )
    (comp (ref "TVS35")
      (value "PSD05C-LF-T7")
      (footprint "SOD-323")
      (description "单向TVS")
      (libsource (lib "XiaoyI") (part "TVS-S"))
    )
    (comp (ref "TVS36")
      (value "PSD05C-LF-T7")
      (footprint "SOD-323")
      (description "单向TVS")
      (libsource (lib "XiaoyI") (part "TVS-S"))
    )
    (comp (ref "U8")
      (value "OPA2376AID/NC")
      (footprint "SOIC-8")
      (description "运放")
      (libsource (lib "XiaoyI") (part "LM358"))
    )
    (comp (ref "U9")
      (value "ADS1299IPAG")
      (footprint "LQFP-64")
      (libsource (lib "stm32") (part "ADS1299IPAG"))
    )
    (comp (ref "U11")
      (value "OPA2376AID/NC")
      (footprint "SOIC-8")
      (description "运放")
      (libsource (lib "XiaoyI") (part "LM358"))
    )
    (comp (ref "U12")
      (value "OPA2376AID/NC")
      (footprint "SOIC-8")
      (description "运放")
      (libsource (lib "XiaoyI") (part "LM358"))
    )
    (comp (ref "U13")
      (value "ADS1299IPAG")
      (footprint "LQFP-64")
      (libsource (lib "stm32") (part "ADS1299IPAG"))
    )
    (comp (ref "U14")
      (value "OPA2376AID/NC")
      (footprint "SOIC-8")
      (description "运放")
      (libsource (lib "XiaoyI") (part "LM358"))
    )
  )
  (nets
    (net (code "1") (name "/ADC_SPO") (class "Default")
      (node (ref "P1") (pin "12") (pinfunction "12_12") (pintype "passive"))
    )
    (net (code "2") (name "/ADS129x_CS") (class "Default")
      (node (ref "P1") (pin "7") (pinfunction "7_7") (pintype "passive"))
      (node (ref "U9") (pin "39") (pinfunction "~{CS}_39") (pintype "passive"))
    )
    (net (code "3") (name "/ADS129x_CS2") (class "Default")
      (node (ref "P1") (pin "9") (pinfunction "9_9") (pintype "passive"))
      (node (ref "U13") (pin "39") (pinfunction "~{CS}_39") (pintype "passive"))
    )
    (net (code "4") (name "/ADS129x_DIN") (class "Default")
      (node (ref "P1") (pin "10") (pinfunction "10_10") (pintype "passive"))
      (node (ref "U13") (pin "34") (pinfunction "DIN_34") (pintype "passive"))
      (node (ref "U9") (pin "34") (pinfunction "DIN_34") (pintype "passive"))
    )
    (net (code "5") (name "/ADS129x_DOUT") (class "Default")
      (node (ref "P1") (pin "3") (pinfunction "3_3") (pintype "passive"))
      (node (ref "U13") (pin "43") (pinfunction "DOUT_43") (pintype "passive"))
      (node (ref "U9") (pin "43") (pinfunction "DOUT_43") (pintype "passive"))
    )
    (net (code "6") (name "/ADS129x_DRDY") (class "Default")
      (node (ref "P1") (pin "1") (pinfunction "1_1") (pintype "passive"))
      (node (ref "U9") (pin "47") (pinfunction "~{DRDY}_47") (pintype "passive"))
    )
    (net (code "7") (name "/ADS129x_DRDY2") (class "Default")
      (node (ref "P1") (pin "11") (pinfunction "11_11") (pintype "passive"))
      (node (ref "U13") (pin "47") (pinfunction "~{DRDY}_47") (pintype "passive"))
    )
    (net (code "8") (name "/ADS129x_SCLK") (class "Default")
      (node (ref "P1") (pin "5") (pinfunction "5_5") (pintype "passive"))
      (node (ref "U13") (pin "40") (pinfunction "SCLK_40") (pintype "passive"))
      (node (ref "U9") (pin "40") (pinfunction "SCLK_40") (pintype "passive"))
    )
    (net (code "9") (name "/BIAS_ELEC") (class "Default")
      (node (ref "P12") (pin "1") (pinfunction "1_1") (pintype "passive"))
      (node (ref "P13") (pin "1") (pinfunction "1_1") (pintype "passive"))
    )
    (net (code "10") (name "/BIAS_ELEC2") (class "Default")
      (node (ref "P18") (pin "1") (pinfunction "1_1") (pintype "passive"))
      (node (ref "P19") (pin "1") (pinfunction "1_1") (pintype "passive"))
    )
    (net (code "11") (name "/BIAS_SHD") (class "Default")
      (node (ref "U8") (pin "1") (pinfunction "OUT1_1") (pintype "output"))
      (node (ref "U8") (pin "2") (pinfunction "IN1-_2") (pintype "input"))
    )
    (net (code "12") (name "/BIAS_SHD2") (class "Default")
      (node (ref "U12") (pin "1") (pinfunction "OUT1_1") (pintype "output"))
      (node (ref "U12") (pin "2") (pinfunction "IN1-_2") (pintype "input"))
    )
    (net (code "13") (name "/CIN2P") (class "Default")
      (node (ref "P29") (pin "17") (pinfunction "17_17") (pintype "passive"))
      (node (ref "P29") (pin "19") (pinfunction "19_19") (pintype "passive"))
      (node (ref "P29") (pin "21") (pinfunction "21_21") (pintype "passive"))
      (node (ref "P29") (pin "22") (pinfunction "22_22") (pintype "passive"))
      (node (ref "P29") (pin "23") (pinfunction "23_23") (pintype "passive"))
      (node (ref "P29") (pin "24") (pinfunction "24_24") (pintype "passive"))
      (node (ref "P29") (pin "25") (pinfunction "25_25") (pintype "passive"))
      (node (ref "P29") (pin "26") (pinfunction "26_26") (pintype "passive"))
      (node (ref "R111") (pin "1") (pinfunction "1_1") (pintype "passive"))
    )
    (net (code "14") (name "/CINN1") (class "Default")
      (node (ref "P16") (pin "2") (pinfunction "2_2") (pintype "passive"))
      (node (ref "R62") (pin "1") (pinfunction "1_1") (pintype "passive"))
    )
    (net (code "15") (name "/CINN2") (class "Default")
      (node (ref "P16") (pin "4") (pinfunction "4_4") (pintype "passive"))
      (node (ref "R69") (pin "1") (pinfunction "1_1") (pintype "passive"))
    )
    (net (code "16") (name "/CINN3") (class "Default")
      (node (ref "P16") (pin "6") (pinfunction "6_6") (pintype "passive"))
      (node (ref "R74") (pin "1") (pinfunction "1_1") (pintype "passive"))
    )
    (net (code "17") (name "/CINN4") (class "Default")
      (node (ref "P16") (pin "8") (pinfunction "8_8") (pintype "passive"))
      (node (ref "R81") (pin "1") (pinfunction "1_1") (pintype "passive"))
    )
    (net (code "18") (name "/CINN5") (class "Default")
      (node (ref "P16") (pin "10") (pinfunction "10_10") (pintype "passive"))
      (node (ref "R86") (pin "1") (pinfunction "1_1") (pintype "passive"))
    )
    (net (code "19") (name "/CINN6") (class "Default")
      (node (ref "P16") (pin "12") (pinfunction "12_12") (pintype "passive"))
      (node (ref "R90") (pin "1") (pinfunction "1_1") (pintype "passive"))
    )
    (net (code "20") (name "/CINN7") (class "Default")
      (node (ref "P16") (pin "14") (pinfunction "14_14") (pintype "passive"))
      (node (ref "R95") (pin "1") (pinfunction "1_1") (pintype "passive"))
    )
    (net (code "21") (name "/CINN8") (class "Default")
      (node (ref "P16") (pin "16") (pinfunction "16_16") (pintype "passive"))
      (node (ref "R99") (pin "1") (pinfunction "1_1") (pintype "passive"))
    )
    (net (code "22") (name "/CINN21") (class "Default")
      (node (ref "P29") (pin "2") (pinfunction "2_2") (pintype "passive"))
      (node (ref "R108") (pin "1") (pinfunction "1_1") (pintype "passive"))
    )
    (net (code "23") (name "/CINN22") (class "Default")
      (node (ref "P29") (pin "4") (pinfunction "4_4") (pintype "passive"))
      (node (ref "R115") (pin "1") (pinfunction "1_1") (pintype "passive"))
    )
    (net (code "24") (name "/CINN23") (class "Default")
      (node (ref "P29") (pin "6") (pinfunction "6_6") (pintype "passive"))
      (node (ref "R120") (pin "1") (pinfunction "1_1") (pintype "passive"))
    )
    (net (code "25") (name "/CINN24") (class "Default")
      (node (ref "P29") (pin "8") (pinfunction "8_8") (pintype "passive"))
      (node (ref "R125") (pin "1") (pinfunction "1_1") (pintype "passive"))
    )
    (net (code "26") (name "/CINN25") (class "Default")
      (node (ref "P29") (pin "10") (pinfunction "10_10") (pintype "passive"))
      (node (ref "R130") (pin "1") (pinfunction "1_1") (pintype "passive"))
    )
    (net (code "27") (name "/CINN26") (class "Default")
      (node (ref "P29") (pin "12") (pinfunction "12_12") (pintype "passive"))
      (node (ref "R134") (pin "1") (pinfunction "1_1") (pintype "passive"))
    )
    (net (code "28") (name "/CINN27") (class "Default")
      (node (ref "P29") (pin "14") (pinfunction "14_14") (pintype "passive"))
      (node (ref "R139") (pin "1") (pinfunction "1_1") (pintype "passive"))
    )
    (net (code "29") (name "/CINN28") (class "Default")
      (node (ref "P29") (pin "16") (pinfunction "16_16") (pintype "passive"))
      (node (ref "R143") (pin "1") (pinfunction "1_1") (pintype "passive"))
    )
    (net (code "30") (name "/CINP") (class "Default")
      (node (ref "P16") (pin "17") (pinfunction "17_17") (pintype "passive"))
      (node (ref "P16") (pin "19") (pinfunction "19_19") (pintype "passive"))
      (node (ref "P16") (pin "21") (pinfunction "21_21") (pintype "passive"))
      (node (ref "P16") (pin "22") (pinfunction "22_22") (pintype "passive"))
      (node (ref "P16") (pin "23") (pinfunction "23_23") (pintype "passive"))
      (node (ref "P16") (pin "24") (pinfunction "24_24") (pintype "passive"))
      (node (ref "P16") (pin "25") (pinfunction "25_25") (pintype "passive"))
      (node (ref "P16") (pin "26") (pinfunction "26_26") (pintype "passive"))
      (node (ref "R65") (pin "1") (pinfunction "1_1") (pintype "passive"))
    )
    (net (code "31") (name "/CINP1") (class "Default")
      (node (ref "P16") (pin "1") (pinfunction "1_1") (pintype "passive"))
      (node (ref "R60") (pin "1") (pinfunction "1_1") (pintype "passive"))
    )
    (net (code "32") (name "/CINP2") (class "Default")
      (node (ref "P16") (pin "3") (pinfunction "3_3") (pintype "passive"))
      (node (ref "R67") (pin "1") (pinfunction "1_1") (pintype "passive"))
    )
    (net (code "33") (name "/CINP3") (class "Default")
      (node (ref "P16") (pin "5") (pinfunction "5_5") (pintype "passive"))
      (node (ref "R72") (pin "1") (pinfunction "1_1") (pintype "passive"))
    )
    (net (code "34") (name "/CINP4") (class "Default")
      (node (ref "P16") (pin "7") (pinfunction "7_7") (pintype "passive"))
      (node (ref "R77") (pin "1") (pinfunction "1_1") (pintype "passive"))
    )
    (net (code "35") (name "/CINP5") (class "Default")
      (node (ref "P16") (pin "9") (pinfunction "9_9") (pintype "passive"))
      (node (ref "R84") (pin "1") (pinfunction "1_1") (pintype "passive"))
    )
    (net (code "36") (name "/CINP6") (class "Default")
      (node (ref "P16") (pin "11") (pinfunction "11_11") (pintype "passive"))
      (node (ref "R88") (pin "1") (pinfunction "1_1") (pintype "passive"))
    )
    (net (code "37") (name "/CINP7") (class "Default")
      (node (ref "P16") (pin "13") (pinfunction "13_13") (pintype "passive"))
      (node (ref "R93") (pin "1") (pinfunction "1_1") (pintype "passive"))
    )
    (net (code "38") (name "/CINP8") (class "Default")
      (node (ref "P16") (pin "15") (pinfunction "15_15") (pintype "passive"))
      (node (ref "R97") (pin "1") (pinfunction "1_1") (pintype "passive"))
    )
    (net (code "39") (name "/CINP21") (class "Default")
      (node (ref "P29") (pin "1") (pinfunction "1_1") (pintype "passive"))
      (node (ref "R106") (pin "1") (pinfunction "1_1") (pintype "passive"))
    )
    (net (code "40") (name "/CINP22") (class "Default")
      (node (ref "P29") (pin "3") (pinfunction "3_3") (pintype "passive"))
      (node (ref "R113") (pin "1") (pinfunction "1_1") (pintype "passive"))
    )
    (net (code "41") (name "/CINP23") (class "Default")
      (node (ref "P29") (pin "5") (pinfunction "5_5") (pintype "passive"))
      (node (ref "R118") (pin "1") (pinfunction "1_1") (pintype "passive"))
    )
    (net (code "42") (name "/CINP24") (class "Default")
      (node (ref "P29") (pin "7") (pinfunction "7_7") (pintype "passive"))
      (node (ref "R123") (pin "1") (pinfunction "1_1") (pintype "passive"))
    )
    (net (code "43") (name "/CINP25") (class "Default")
      (node (ref "P29") (pin "9") (pinfunction "9_9") (pintype "passive"))
      (node (ref "R128") (pin "1") (pinfunction "1_1") (pintype "passive"))
    )
    (net (code "44") (name "/CINP26") (class "Default")
      (node (ref "P29") (pin "11") (pinfunction "11_11") (pintype "passive"))
      (node (ref "R132") (pin "1") (pinfunction "1_1") (pintype "passive"))
    )
    (net (code "45") (name "/CINP27") (class "Default")
      (node (ref "P29") (pin "13") (pinfunction "13_13") (pintype "passive"))
      (node (ref "R137") (pin "1") (pinfunction "1_1") (pintype "passive"))
    )
    (net (code "46") (name "/CINP28") (class "Default")
      (node (ref "P29") (pin "15") (pinfunction "15_15") (pintype "passive"))
      (node (ref "R141") (pin "1") (pinfunction "1_1") (pintype "passive"))
    )
    (net (code "47") (name "/IN1N") (class "Default")
      (node (ref "C46") (pin "2") (pinfunction "2_2") (pintype "passive"))
      (node (ref "R63") (pin "2") (pinfunction "2_2") (pintype "passive"))
      (node (ref "TVS2") (pin "2") (pinfunction "B_2") (pintype "passive"))
      (node (ref "U9") (pin "15") (pinfunction "IN1N_15") (pintype "passive"))
    )
    (net (code "48") (name "/IN1P") (class "Default")
      (node (ref "C43") (pin "2") (pinfunction "2_2") (pintype "passive"))
      (node (ref "R61") (pin "2") (pinfunction "2_2") (pintype "passive"))
      (node (ref "TVS1") (pin "2") (pinfunction "B_2") (pintype "passive"))
      (node (ref "U9") (pin "16") (pinfunction "IN1P_16") (pintype "passive"))
    )
    (net (code "49") (name "/IN2N") (class "Default")
      (node (ref "C58") (pin "2") (pinfunction "2_2") (pintype "passive"))
      (node (ref "R70") (pin "2") (pinfunction "2_2") (pintype "passive"))
      (node (ref "TVS7") (pin "2") (pinfunction "B_2") (pintype "passive"))
      (node (ref "U9") (pin "13") (pinfunction "IN2N_13") (pintype "passive"))
    )
    (net (code "50") (name "/IN2P") (class "Default")
      (node (ref "C53") (pin "2") (pinfunction "2_2") (pintype "passive"))
      (node (ref "R68") (pin "2") (pinfunction "2_2") (pintype "passive"))
      (node (ref "TVS6") (pin "2") (pinfunction "B_2") (pintype "passive"))
      (node (ref "U9") (pin "14") (pinfunction "IN2P_14") (pintype "passive"))
    )
    (net (code "51") (name "/IN3N") (class "Default")
      (node (ref "C62") (pin "2") (pinfunction "2_2") (pintype "passive"))
      (node (ref "R75") (pin "2") (pinfunction "2_2") (pintype "passive"))
      (node (ref "TVS9") (pin "2") (pinfunction "B_2") (pintype "passive"))
      (node (ref "U9") (pin "11") (pinfunction "IN3N_11") (pintype "passive"))
    )
    (net (code "52") (name "/IN3P") (class "Default")
      (node (ref "C60") (pin "2") (pinfunction "2_2") (pintype "passive"))
      (node (ref "R73") (pin "2") (pinfunction "2_2") (pintype "passive"))
      (node (ref "TVS8") (pin "2") (pinfunction "B_2") (pintype "passive"))
      (node (ref "U9") (pin "12") (pinfunction "IN3P_12") (pintype "passive"))
    )
    (net (code "53") (name "/IN4N") (class "Default")
      (node (ref "C66") (pin "2") (pinfunction "2_2") (pintype "passive"))
      (node (ref "R82") (pin "2") (pinfunction "2_2") (pintype "passive"))
      (node (ref "TVS11") (pin "2") (pinfunction "B_2") (pintype "passive"))
      (node (ref "U9") (pin "9") (pinfunction "IN4N_9") (pintype "passive"))
    )
    (net (code "54") (name "/IN4P") (class "Default")
      (node (ref "C64") (pin "2") (pinfunction "2_2") (pintype "passive"))
      (node (ref "R80") (pin "2") (pinfunction "2_2") (pintype "passive"))
      (node (ref "TVS10") (pin "2") (pinfunction "B_2") (pintype "passive"))
      (node (ref "U9") (pin "10") (pinfunction "IN4P_10") (pintype "passive"))
    )
    (net (code "55") (name "/IN5N") (class "Default")
      (node (ref "C70") (pin "2") (pinfunction "2_2") (pintype "passive"))
      (node (ref "R87") (pin "2") (pinfunction "2_2") (pintype "passive"))
      (node (ref "TVS13") (pin "2") (pinfunction "B_2") (pintype "passive"))
      (node (ref "U9") (pin "7") (pinfunction "IN5N_7") (pintype "passive"))
    )
    (net (code "56") (name "/IN5P") (class "Default")
      (node (ref "C68") (pin "2") (pinfunction "2_2") (pintype "passive"))
      (node (ref "R85") (pin "2") (pinfunction "2_2") (pintype "passive"))
      (node (ref "TVS12") (pin "2") (pinfunction "B_2") (pintype "passive"))
      (node (ref "U9") (pin "8") (pinfunction "IN5P_8") (pintype "passive"))
    )
    (net (code "57") (name "/IN6N") (class "Default")
      (node (ref "C75") (pin "2") (pinfunction "2_2") (pintype "passive"))
      (node (ref "R91") (pin "2") (pinfunction "2_2") (pintype "passive"))
      (node (ref "TVS15") (pin "2") (pinfunction "B_2") (pintype "passive"))
      (node (ref "U9") (pin "5") (pinfunction "IN6N_5") (pintype "passive"))
    )
    (net (code "58") (name "/IN6P") (class "Default")
      (node (ref "C73") (pin "2") (pinfunction "2_2") (pintype "passive"))
      (node (ref "R89") (pin "2") (pinfunction "2_2") (pintype "passive"))
      (node (ref "TVS14") (pin "2") (pinfunction "B_2") (pintype "passive"))
      (node (ref "U9") (pin "6") (pinfunction "IN6P_6") (pintype "passive"))
    )
    (net (code "59") (name "/IN7N") (class "Default")
      (node (ref "C85") (pin "2") (pinfunction "2_2") (pintype "passive"))
      (node (ref "R96") (pin "2") (pinfunction "2_2") (pintype "passive"))
      (node (ref "TVS17") (pin "2") (pinfunction "B_2") (pintype "passive"))
      (node (ref "U9") (pin "3") (pinfunction "IN7N_3") (pintype "passive"))
    )
    (net (code "60") (name "/IN7P") (class "Default")
      (node (ref "C83") (pin "2") (pinfunction "2_2") (pintype "passive"))
      (node (ref "R94") (pin "2") (pinfunction "2_2") (pintype "passive"))
      (node (ref "TVS16") (pin "2") (pinfunction "B_2") (pintype "passive"))
      (node (ref "U9") (pin "4") (pinfunction "IN7P_4") (pintype "passive"))
    )
    (net (code "61") (name "/IN8N") (class "Default")
      (node (ref "C89") (pin "2") (pinfunction "2_2") (pintype "passive"))
      (node (ref "R100") (pin "2") (pinfunction "2_2") (pintype "passive"))
      (node (ref "TVS19") (pin "2") (pinfunction "B_2") (pintype "passive"))
      (node (ref "U9") (pin "1") (pinfunction "IN8N_1") (pintype "passive"))
    )
    (net (code "62") (name "/IN8P") (class "Default")
      (node (ref "C87") (pin "2") (pinfunction "2_2") (pintype "passive"))
      (node (ref "R98") (pin "2") (pinfunction "2_2") (pintype "passive"))
      (node (ref "TVS18") (pin "2") (pinfunction "B_2") (pintype "passive"))
      (node (ref "U9") (pin "2") (pinfunction "IN8P_2") (pintype "passive"))
    )
    (net (code "63") (name "/IN21N") (class "Default")
      (node (ref "C105") (pin "2") (pinfunction "2_2") (pintype "passive"))
      (node (ref "R109") (pin "2") (pinfunction "2_2") (pintype "passive"))
      (node (ref "TVS21") (pin "2") (pinfunction "B_2") (pintype "passive"))
      (node (ref "U13") (pin "15") (pinfunction "IN1N_15") (pintype "passive"))
    )
    (net (code "64") (name "/IN21P") (class "Default")
      (node (ref "C103") (pin "2") (pinfunction "2_2") (pintype "passive"))
      (node (ref "R107") (pin "2") (pinfunction "2_2") (pintype "passive"))
      (node (ref "TVS20") (pin "2") (pinfunction "B_2") (pintype "passive"))
      (node (ref "U13") (pin "16") (pinfunction "IN1P_16") (pintype "passive"))
    )
    (net (code "65") (name "/IN22N") (class "Default")
      (node (ref "C111") (pin "2") (pinfunction "2_2") (pintype "passive"))
      (node (ref "R116") (pin "2") (pinfunction "2_2") (pintype "passive"))
      (node (ref "TVS24") (pin "2") (pinfunction "B_2") (pintype "passive"))
      (node (ref "U13") (pin "13") (pinfunction "IN2N_13") (pintype "passive"))
    )
    (net (code "66") (name "/IN22P") (class "Default")
      (node (ref "C109") (pin "2") (pinfunction "2_2") (pintype "passive"))
      (node (ref "R114") (pin "2") (pinfunction "2_2") (pintype "passive"))
      (node (ref "TVS23") (pin "2") (pinfunction "B_2") (pintype "passive"))
      (node (ref "U13") (pin "14") (pinfunction "IN2P_14") (pintype "passive"))
    )
    (net (code "67") (name "/IN23N") (class "Default")
      (node (ref "C115") (pin "2") (pinfunction "2_2") (pintype "passive"))
      (node (ref "R121") (pin "2") (pinfunction "2_2") (pintype "passive"))
      (node (ref "TVS26") (pin "2") (pinfunction "B_2") (pintype "passive"))
      (node (ref "U13") (pin "11") (pinfunction "IN3N_11") (pintype "passive"))
    )
    (net (code "68") (name "/IN23P") (class "Default")
      (node (ref "C113") (pin "2") (pinfunction "2_2") (pintype "passive"))
      (node (ref "R119") (pin "2") (pinfunction "2_2") (pintype "passive"))
      (node (ref "TVS25") (pin "2") (pinfunction "B_2") (pintype "passive"))
      (node (ref "U13") (pin "12") (pinfunction "IN3P_12") (pintype "passive"))
    )
    (net (code "69") (name "/IN24N") (class "Default")
      (node (ref "C119") (pin "2") (pinfunction "2_2") (pintype "passive"))
      (node (ref "R126") (pin "2") (pinfunction "2_2") (pintype "passive"))
      (node (ref "TVS28") (pin "2") (pinfunction "B_2") (pintype "passive"))
      (node (ref "U13") (pin "9") (pinfunction "IN4N_9") (pintype "passive"))
    )
    (net (code "70") (name "/IN24P") (class "Default")
      (node (ref "C117") (pin "2") (pinfunction "2_2") (pintype "passive"))
      (node (ref "R124") (pin "2") (pinfunction "2_2") (pintype "passive"))
      (node (ref "TVS27") (pin "2") (pinfunction "B_2") (pintype "passive"))
      (node (ref "U13") (pin "10") (pinfunction "IN4P_10") (pintype "passive"))
    )
    (net (code "71") (name "/IN25N") (class "Default")
      (node (ref "C123") (pin "2") (pinfunction "2_2") (pintype "passive"))
      (node (ref "R131") (pin "2") (pinfunction "2_2") (pintype "passive"))
      (node (ref "TVS30") (pin "2") (pinfunction "B_2") (pintype "passive"))
      (node (ref "U13") (pin "7") (pinfunction "IN5N_7") (pintype "passive"))
    )
    (net (code "72") (name "/IN25P") (class "Default")
      (node (ref "C121") (pin "2") (pinfunction "2_2") (pintype "passive"))
      (node (ref "R129") (pin "2") (pinfunction "2_2") (pintype "passive"))
      (node (ref "TVS29") (pin "2") (pinfunction "B_2") (pintype "passive"))
      (node (ref "U13") (pin "8") (pinfunction "IN5P_8") (pintype "passive"))
    )
    (net (code "73") (name "/IN26N") (class "Default")
      (node (ref "C128") (pin "2") (pinfunction "2_2") (pintype "passive"))
      (node (ref "R135") (pin "2") (pinfunction "2_2") (pintype "passive"))
      (node (ref "TVS32") (pin "2") (pinfunction "B_2") (pintype "passive"))
      (node (ref "U13") (pin "5") (pinfunction "IN6N_5") (pintype "passive"))
    )
    (net (code "74") (name "/IN26P") (class "Default")
      (node (ref "C126") (pin "2") (pinfunction "2_2") (pintype "passive"))
      (node (ref "R133") (pin "2") (pinfunction "2_2") (pintype "passive"))
      (node (ref "TVS31") (pin "2") (pinfunction "B_2") (pintype "passive"))
      (node (ref "U13") (pin "6") (pinfunction "IN6P_6") (pintype "passive"))
    )
    (net (code "75") (name "/IN27N") (class "Default")
      (node (ref "C138") (pin "2") (pinfunction "2_2") (pintype "passive"))
      (node (ref "R140") (pin "2") (pinfunction "2_2") (pintype "passive"))
      (node (ref "TVS34") (pin "2") (pinfunction "B_2") (pintype "passive"))
      (node (ref "U13") (pin "3") (pinfunction "IN7N_3") (pintype "passive"))
    )
    (net (code "76") (name "/IN27P") (class "Default")
      (node (ref "C136") (pin "2") (pinfunction "2_2") (pintype "passive"))
      (node (ref "R138") (pin "2") (pinfunction "2_2") (pintype "passive"))
      (node (ref "TVS33") (pin "2") (pinfunction "B_2") (pintype "passive"))
      (node (ref "U13") (pin "4") (pinfunction "IN7P_4") (pintype "passive"))
    )
    (net (code "77") (name "/IN28N") (class "Default")
      (node (ref "C142") (pin "2") (pinfunction "2_2") (pintype "passive"))
      (node (ref "R144") (pin "2") (pinfunction "2_2") (pintype "passive"))
      (node (ref "TVS36") (pin "2") (pinfunction "B_2") (pintype "passive"))
      (node (ref "U13") (pin "1") (pinfunction "IN8N_1") (pintype "passive"))
    )
    (net (code "78") (name "/IN28P") (class "Default")
      (node (ref "C140") (pin "2") (pinfunction "2_2") (pintype "passive"))
      (node (ref "R142") (pin "2") (pinfunction "2_2") (pintype "passive"))
      (node (ref "TVS35") (pin "2") (pinfunction "B_2") (pintype "passive"))
      (node (ref "U13") (pin "2") (pinfunction "IN8P_2") (pintype "passive"))
    )
    (net (code "79") (name "/TA") (class "Default")
      (node (ref "P2") (pin "6") (pinfunction "6_6") (pintype "passive"))
    )
    (net (code "80") (name "/TB") (class "Default")
      (node (ref "P2") (pin "5") (pinfunction "5_5") (pintype "passive"))
    )
    (net (code "81") (name "/out1") (class "Default")
      (node (ref "P2") (pin "1") (pinfunction "1_1") (pintype "passive"))
    )
    (net (code "82") (name "/out2") (class "Default")
      (node (ref "P2") (pin "2") (pinfunction "2_2") (pintype "passive"))
    )
    (net (code "83") (name "/out3") (class "Default")
      (node (ref "P2") (pin "3") (pinfunction "3_3") (pintype "passive"))
    )
    (net (code "84") (name "/out4") (class "Default")
      (node (ref "P2") (pin "4") (pinfunction "4_4") (pintype "passive"))
    )
    (net (code "85") (name "AVDD") (class "Default")
      (node (ref "C124") (pin "2") (pinfunction "2_2") (pintype "passive"))
      (node (ref "C143") (pin "2") (pinfunction "2_2") (pintype "passive"))
      (node (ref "C144") (pin "2") (pinfunction "2_2") (pintype "passive"))
      (node (ref "C145") (pin "2") (pinfunction "2_2") (pintype "passive"))
      (node (ref "C146") (pin "2") (pinfunction "2_2") (pintype "passive"))
      (node (ref "C147") (pin "2") (pinfunction "2_2") (pintype "passive"))
      (node (ref "C35") (pin "2") (pinfunction "2_2") (pintype "passive"))
      (node (ref "C71") (pin "2") (pinfunction "2_2") (pintype "passive"))
      (node (ref "C90") (pin "2") (pinfunction "2_2") (pintype "passive"))
      (node (ref "C91") (pin "2") (pinfunction "2_2") (pintype "passive"))
      (node (ref "C92") (pin "2") (pinfunction "2_2") (pintype "passive"))
      (node (ref "C93") (pin "2") (pinfunction "2_2") (pintype "passive"))
      (node (ref "C94") (pin "2") (pinfunction "2_2") (pintype "passive"))
      (node (ref "C98") (pin "2") (pinfunction "2_2") (pintype "passive"))
      (node (ref "P1") (pin "2") (pinfunction "2_2") (pintype "passive"))
      (node (ref "R103") (pin "1") (pinfunction "1_1") (pintype "passive"))
      (node (ref "R117") (pin "1") (pinfunction "1_1") (pintype "passive"))
      (node (ref "R53") (pin "1") (pinfunction "1_1") (pintype "passive"))
      (node (ref "R71") (pin "1") (pinfunction "1_1") (pintype "passive"))
      (node (ref "U11") (pin "8") (pinfunction "V+_8") (pintype "power_in"))
      (node (ref "U12") (pin "8") (pinfunction "V+_8") (pintype "power_in"))
      (node (ref "U13") (pin "19") (pinfunction "AVDD_19") (pintype "passive"))
      (node (ref "U13") (pin "21") (pinfunction "AVDD_21") (pintype "passive"))
      (node (ref "U13") (pin "22") (pinfunction "AVDD_22") (pintype "passive"))
      (node (ref "U13") (pin "54") (pinfunction "AVDD1_54") (pintype "passive"))
      (node (ref "U13") (pin "56") (pinfunction "AVDD_56") (pintype "passive"))
      (node (ref "U13") (pin "59") (pinfunction "AVDD_59") (pintype "passive"))
      (node (ref "U14") (pin "8") (pinfunction "V+_8") (pintype "power_in"))
      (node (ref "U8") (pin "8") (pinfunction "V+_8") (pintype "power_in"))
      (node (ref "U9") (pin "19") (pinfunction "AVDD_19") (pintype "passive"))
      (node (ref "U9") (pin "21") (pinfunction "AVDD_21") (pintype "passive"))
      (node (ref "U9") (pin "22") (pinfunction "AVDD_22") (pintype "passive"))
      (node (ref "U9") (pin "54") (pinfunction "AVDD1_54") (pintype "passive"))
      (node (ref "U9") (pin "56") (pinfunction "AVDD_56") (pintype "passive"))
      (node (ref "U9") (pin "59") (pinfunction "AVDD_59") (pintype "passive"))
    )
    (net (code "86") (name "AVSS") (class "Default")
      (node (ref "C102") (pin "1") (pinfunction "1_1") (pintype "passive"))
      (node (ref "C103") (pin "1") (pinfunction "1_1") (pintype "passive"))
      (node (ref "C104") (pin "1") (pinfunction "1_1") (pintype "passive"))
      (node (ref "C105") (pin "1") (pinfunction "1_1") (pintype "passive"))
      (node (ref "C106") (pin "1") (pinfunction "1_1") (pintype "passive"))
      (node (ref "C107") (pin "1") (pinfunction "1_1") (pintype "passive"))
      (node (ref "C108") (pin "1") (pinfunction "1_1") (pintype "passive"))
      (node (ref "C109") (pin "1") (pinfunction "1_1") (pintype "passive"))
      (node (ref "C110") (pin "1") (pinfunction "1_1") (pintype "passive"))
      (node (ref "C111") (pin "1") (pinfunction "1_1") (pintype "passive"))
      (node (ref "C112") (pin "1") (pinfunction "1_1") (pintype "passive"))
      (node (ref "C113") (pin "1") (pinfunction "1_1") (pintype "passive"))
      (node (ref "C114") (pin "1") (pinfunction "1_1") (pintype "passive"))
      (node (ref "C115") (pin "1") (pinfunction "1_1") (pintype "passive"))
      (node (ref "C116") (pin "1") (pinfunction "1_1") (pintype "passive"))
      (node (ref "C117") (pin "1") (pinfunction "1_1") (pintype "passive"))
      (node (ref "C118") (pin "1") (pinfunction "1_1") (pintype "passive"))
      (node (ref "C119") (pin "1") (pinfunction "1_1") (pintype "passive"))
      (node (ref "C120") (pin "1") (pinfunction "1_1") (pintype "passive"))
      (node (ref "C121") (pin "1") (pinfunction "1_1") (pintype "passive"))
      (node (ref "C122") (pin "1") (pinfunction "1_1") (pintype "passive"))
      (node (ref "C123") (pin "1") (pinfunction "1_1") (pintype "passive"))
      (node (ref "C124") (pin "1") (pinfunction "1_1") (pintype "passive"))
      (node (ref "C125") (pin "1") (pinfunction "1_1") (pintype "passive"))
      (node (ref "C126") (pin "1") (pinfunction "1_1") (pintype "passive"))
      (node (ref "C127") (pin "1") (pinfunction "1_1") (pintype "passive"))
      (node (ref "C128") (pin "1") (pinfunction "1_1") (pintype "passive"))
      (node (ref "C129") (pin "1") (pinfunction "1_1") (pintype "passive"))
      (node (ref "C130") (pin "1") (pinfunction "1_1") (pintype "passive"))
      (node (ref "C131") (pin "1") (pinfunction "1_1") (pintype "passive"))
      (node (ref "C132") (pin "1") (pinfunction "1_1") (pintype "passive"))
      (node (ref "C133") (pin "1") (pinfunction "1_1") (pintype "passive"))
      (node (ref "C134") (pin "1") (pinfunction "1_1") (pintype "passive"))
      (node (ref "C135") (pin "1") (pinfunction "1_1") (pintype "passive"))
      (node (ref "C136") (pin "1") (pinfunction "1_1") (pintype "passive"))
      (node (ref "C137") (pin "1") (pinfunction "1_1") (pintype "passive"))
      (node (ref "C138") (pin "1") (pinfunction "1_1") (pintype "passive"))
      (node (ref "C139") (pin "1") (pinfunction "1_1") (pintype "passive"))
      (node (ref "C140") (pin "1") (pinfunction "1_1") (pintype "passive"))
      (node (ref "C141") (pin "1") (pinfunction "1_1") (pintype "passive"))
      (node (ref "C142") (pin "1") (pinfunction "1_1") (pintype "passive"))
      (node (ref "C143") (pin "1") (pinfunction "1_1") (pintype "passive"))
      (node (ref "C144") (pin "1") (pinfunction "1_1") (pintype "passive"))
      (node (ref "C145") (pin "1") (pinfunction "1_1") (pintype "passive"))
      (node (ref "C146") (pin "1") (pinfunction "1_1") (pintype "passive"))
      (node (ref "C147") (pin "1") (pinfunction "1_1") (pintype "passive"))
      (node (ref "C35") (pin "1") (pinfunction "1_1") (pintype "passive"))
      (node (ref "C42") (pin "1") (pinfunction "1_1") (pintype "passive"))
      (node (ref "C43") (pin "1") (pinfunction "1_1") (pintype "passive"))
      (node (ref "C44") (pin "1") (pinfunction "1_1") (pintype "passive"))
      (node (ref "C46") (pin "1") (pinfunction "1_1") (pintype "passive"))
      (node (ref "C47") (pin "1") (pinfunction "1_1") (pintype "passive"))
      (node (ref "C48") (pin "1") (pinfunction "1_1") (pintype "passive"))
      (node (ref "C49") (pin "1") (pinfunction "1_1") (pintype "passive"))
      (node (ref "C53") (pin "1") (pinfunction "1_1") (pintype "passive"))
      (node (ref "C54") (pin "1") (pinfunction "1_1") (pintype "passive"))
      (node (ref "C58") (pin "1") (pinfunction "1_1") (pintype "passive"))
      (node (ref "C59") (pin "1") (pinfunction "1_1") (pintype "passive"))
      (node (ref "C60") (pin "1") (pinfunction "1_1") (pintype "passive"))
      (node (ref "C61") (pin "1") (pinfunction "1_1") (pintype "passive"))
      (node (ref "C62") (pin "1") (pinfunction "1_1") (pintype "passive"))
      (node (ref "C63") (pin "1") (pinfunction "1_1") (pintype "passive"))
      (node (ref "C64") (pin "1") (pinfunction "1_1") (pintype "passive"))
      (node (ref "C65") (pin "1") (pinfunction "1_1") (pintype "passive"))
      (node (ref "C66") (pin "1") (pinfunction "1_1") (pintype "passive"))
      (node (ref "C67") (pin "1") (pinfunction "1_1") (pintype "passive"))
      (node (ref "C68") (pin "1") (pinfunction "1_1") (pintype "passive"))
      (node (ref "C69") (pin "1") (pinfunction "1_1") (pintype "passive"))
      (node (ref "C70") (pin "1") (pinfunction "1_1") (pintype "passive"))
      (node (ref "C71") (pin "1") (pinfunction "1_1") (pintype "passive"))
      (node (ref "C72") (pin "1") (pinfunction "1_1") (pintype "passive"))
      (node (ref "C73") (pin "1") (pinfunction "1_1") (pintype "passive"))
      (node (ref "C74") (pin "1") (pinfunction "1_1") (pintype "passive"))
      (node (ref "C75") (pin "1") (pinfunction "1_1") (pintype "passive"))
      (node (ref "C76") (pin "1") (pinfunction "1_1") (pintype "passive"))
      (node (ref "C77") (pin "1") (pinfunction "1_1") (pintype "passive"))
      (node (ref "C78") (pin "1") (pinfunction "1_1") (pintype "passive"))
      (node (ref "C79") (pin "1") (pinfunction "1_1") (pintype "passive"))
      (node (ref "C80") (pin "1") (pinfunction "1_1") (pintype "passive"))
      (node (ref "C81") (pin "1") (pinfunction "1_1") (pintype "passive"))
      (node (ref "C82") (pin "1") (pinfunction "1_1") (pintype "passive"))
      (node (ref "C83") (pin "1") (pinfunction "1_1") (pintype "passive"))
      (node (ref "C84") (pin "1") (pinfunction "1_1") (pintype "passive"))
      (node (ref "C85") (pin "1") (pinfunction "1_1") (pintype "passive"))
      (node (ref "C86") (pin "1") (pinfunction "1_1") (pintype "passive"))
      (node (ref "C87") (pin "1") (pinfunction "1_1") (pintype "passive"))
      (node (ref "C88") (pin "1") (pinfunction "1_1") (pintype "passive"))
      (node (ref "C89") (pin "1") (pinfunction "1_1") (pintype "passive"))
      (node (ref "C90") (pin "1") (pinfunction "1_1") (pintype "passive"))
      (node (ref "C91") (pin "1") (pinfunction "1_1") (pintype "passive"))
      (node (ref "C92") (pin "1") (pinfunction "1_1") (pintype "passive"))
      (node (ref "C93") (pin "1") (pinfunction "1_1") (pintype "passive"))
      (node (ref "C94") (pin "1") (pinfunction "1_1") (pintype "passive"))
      (node (ref "C98") (pin "1") (pinfunction "1_1") (pintype "passive"))
      (node (ref "DS10") (pin "2") (pinfunction "2_2") (pintype "passive"))
      (node (ref "DS11") (pin "2") (pinfunction "2_2") (pintype "passive"))
      (node (ref "DS12") (pin "2") (pinfunction "2_2") (pintype "passive"))
      (node (ref "DS13") (pin "2") (pinfunction "2_2") (pintype "passive"))
      (node (ref "DS14") (pin "2") (pinfunction "2_2") (pintype "passive"))
      (node (ref "DS15") (pin "2") (pinfunction "2_2") (pintype "passive"))
      (node (ref "DS16") (pin "2") (pinfunction "2_2") (pintype "passive"))
      (node (ref "DS17") (pin "2") (pinfunction "2_2") (pintype "passive"))
      (node (ref "DS18") (pin "2") (pinfunction "2_2") (pintype "passive"))
      (node (ref "DS19") (pin "2") (pinfunction "2_2") (pintype "passive"))
      (node (ref "DS2") (pin "2") (pinfunction "2_2") (pintype "passive"))
      (node (ref "DS20") (pin "2") (pinfunction "2_2") (pintype "passive"))
      (node (ref "DS21") (pin "2") (pinfunction "2_2") (pintype "passive"))
      (node (ref "DS22") (pin "2") (pinfunction "2_2") (pintype "passive"))
      (node (ref "DS23") (pin "2") (pinfunction "2_2") (pintype "passive"))
      (node (ref "DS24") (pin "2") (pinfunction "2_2") (pintype "passive"))
      (node (ref "DS25") (pin "2") (pinfunction "2_2") (pintype "passive"))
      (node (ref "DS26") (pin "2") (pinfunction "2_2") (pintype "passive"))
      (node (ref "DS27") (pin "2") (pinfunction "2_2") (pintype "passive"))
      (node (ref "DS28") (pin "2") (pinfunction "2_2") (pintype "passive"))
      (node (ref "DS29") (pin "2") (pinfunction "2_2") (pintype "passive"))
      (node (ref "DS3") (pin "2") (pinfunction "2_2") (pintype "passive"))
      (node (ref "DS30") (pin "2") (pinfunction "2_2") (pintype "passive"))
      (node (ref "DS31") (pin "2") (pinfunction "2_2") (pintype "passive"))
      (node (ref "DS32") (pin "2") (pinfunction "2_2") (pintype "passive"))
      (node (ref "DS33") (pin "2") (pinfunction "2_2") (pintype "passive"))
      (node (ref "DS34") (pin "2") (pinfunction "2_2") (pintype "passive"))
      (node (ref "DS35") (pin "2") (pinfunction "2_2") (pintype "passive"))
      (node (ref "DS4") (pin "2") (pinfunction "2_2") (pintype "passive"))
      (node (ref "DS5") (pin "2") (pinfunction "2_2") (pintype "passive"))
      (node (ref "DS6") (pin "2") (pinfunction "2_2") (pintype "passive"))
      (node (ref "DS7") (pin "2") (pinfunction "2_2") (pintype "passive"))
      (node (ref "DS8") (pin "2") (pinfunction "2_2") (pintype "passive"))
      (node (ref "DS9") (pin "2") (pinfunction "2_2") (pintype "passive"))
      (node (ref "P1") (pin "4") (pinfunction "4_4") (pintype "passive"))
      (node (ref "P16") (pin "18") (pinfunction "18_18") (pintype "passive"))
      (node (ref "P16") (pin "20") (pinfunction "20_20") (pintype "passive"))
      (node (ref "P29") (pin "18") (pinfunction "18_18") (pintype "passive"))
      (node (ref "P29") (pin "20") (pinfunction "20_20") (pintype "passive"))
      (node (ref "R104") (pin "1") (pinfunction "1_1") (pintype "passive"))
      (node (ref "R122") (pin "2") (pinfunction "2_2") (pintype "passive"))
      (node (ref "R145") (pin "2") (pinfunction "2_2") (pintype "passive"))
      (node (ref "R54") (pin "1") (pinfunction "1_1") (pintype "passive"))
      (node (ref "R76") (pin "2") (pinfunction "2_2") (pintype "passive"))
      (node (ref "TVS1") (pin "1") (pinfunction "A_1") (pintype "passive"))
      (node (ref "TVS10") (pin "1") (pinfunction "A_1") (pintype "passive"))
      (node (ref "TVS11") (pin "1") (pinfunction "A_1") (pintype "passive"))
      (node (ref "TVS12") (pin "1") (pinfunction "A_1") (pintype "passive"))
      (node (ref "TVS13") (pin "1") (pinfunction "A_1") (pintype "passive"))
      (node (ref "TVS14") (pin "1") (pinfunction "A_1") (pintype "passive"))
      (node (ref "TVS15") (pin "1") (pinfunction "A_1") (pintype "passive"))
      (node (ref "TVS16") (pin "1") (pinfunction "A_1") (pintype "passive"))
      (node (ref "TVS17") (pin "1") (pinfunction "A_1") (pintype "passive"))
      (node (ref "TVS18") (pin "1") (pinfunction "A_1") (pintype "passive"))
      (node (ref "TVS19") (pin "1") (pinfunction "A_1") (pintype "passive"))
      (node (ref "TVS2") (pin "1") (pinfunction "A_1") (pintype "passive"))
      (node (ref "TVS20") (pin "1") (pinfunction "A_1") (pintype "passive"))
      (node (ref "TVS21") (pin "1") (pinfunction "A_1") (pintype "passive"))
      (node (ref "TVS22") (pin "1") (pinfunction "A_1") (pintype "passive"))
      (node (ref "TVS23") (pin "1") (pinfunction "A_1") (pintype "passive"))
      (node (ref "TVS24") (pin "1") (pinfunction "A_1") (pintype "passive"))
      (node (ref "TVS25") (pin "1") (pinfunction "A_1") (pintype "passive"))
      (node (ref "TVS26") (pin "1") (pinfunction "A_1") (pintype "passive"))
      (node (ref "TVS27") (pin "1") (pinfunction "A_1") (pintype "passive"))
      (node (ref "TVS28") (pin "1") (pinfunction "A_1") (pintype "passive"))
      (node (ref "TVS29") (pin "1") (pinfunction "A_1") (pintype "passive"))
      (node (ref "TVS30") (pin "1") (pinfunction "A_1") (pintype "passive"))
      (node (ref "TVS31") (pin "1") (pinfunction "A_1") (pintype "passive"))
      (node (ref "TVS32") (pin "1") (pinfunction "A_1") (pintype "passive"))
      (node (ref "TVS33") (pin "1") (pinfunction "A_1") (pintype "passive"))
      (node (ref "TVS34") (pin "1") (pinfunction "A_1") (pintype "passive"))
      (node (ref "TVS35") (pin "1") (pinfunction "A_1") (pintype "passive"))
      (node (ref "TVS36") (pin "1") (pinfunction "A_1") (pintype "passive"))
      (node (ref "TVS5") (pin "1") (pinfunction "A_1") (pintype "passive"))
      (node (ref "TVS6") (pin "1") (pinfunction "A_1") (pintype "passive"))
      (node (ref "TVS7") (pin "1") (pinfunction "A_1") (pintype "passive"))
      (node (ref "TVS8") (pin "1") (pinfunction "A_1") (pintype "passive"))
      (node (ref "TVS9") (pin "1") (pinfunction "A_1") (pintype "passive"))
      (node (ref "U11") (pin "4") (pinfunction "V-_4") (pintype "power_in"))
      (node (ref "U12") (pin "4") (pinfunction "V-_4") (pintype "power_in"))
      (node (ref "U13") (pin "20") (pinfunction "AVSS_20") (pintype "passive"))
      (node (ref "U13") (pin "23") (pinfunction "AVSS_23") (pintype "passive"))
      (node (ref "U13") (pin "25") (pinfunction "VREFN_25") (pintype "passive"))
      (node (ref "U13") (pin "31") (pinfunction "RESV1_31") (pintype "passive"))
      (node (ref "U13") (pin "32") (pinfunction "AVSS_32") (pintype "passive"))
      (node (ref "U13") (pin "53") (pinfunction "AVSS1_53") (pintype "passive"))
      (node (ref "U13") (pin "57") (pinfunction "AVSS_57") (pintype "passive"))
      (node (ref "U13") (pin "58") (pinfunction "AVSS_58") (pintype "passive"))
      (node (ref "U14") (pin "4") (pinfunction "V-_4") (pintype "power_in"))
      (node (ref "U8") (pin "4") (pinfunction "V-_4") (pintype "power_in"))
      (node (ref "U9") (pin "20") (pinfunction "AVSS_20") (pintype "passive"))
      (node (ref "U9") (pin "23") (pinfunction "AVSS_23") (pintype "passive"))
      (node (ref "U9") (pin "25") (pinfunction "VREFN_25") (pintype "passive"))
      (node (ref "U9") (pin "31") (pinfunction "RESV1_31") (pintype "passive"))
      (node (ref "U9") (pin "32") (pinfunction "AVSS_32") (pintype "passive"))
      (node (ref "U9") (pin "53") (pinfunction "AVSS1_53") (pintype "passive"))
      (node (ref "U9") (pin "57") (pinfunction "AVSS_57") (pintype "passive"))
      (node (ref "U9") (pin "58") (pinfunction "AVSS_58") (pintype "passive"))
    )
    (net (code "87") (name "DVDD") (class "Default")
      (node (ref "C148") (pin "2") (pinfunction "2_2") (pintype "passive"))
      (node (ref "C149") (pin "2") (pinfunction "2_2") (pintype "passive"))
      (node (ref "C150") (pin "2") (pinfunction "2_2") (pintype "passive"))
      (node (ref "C95") (pin "2") (pinfunction "2_2") (pintype "passive"))
      (node (ref "C96") (pin "2") (pinfunction "2_2") (pintype "passive"))
      (node (ref "C97") (pin "2") (pinfunction "2_2") (pintype "passive"))
      (node (ref "P1") (pin "6") (pinfunction "6_6") (pintype "passive"))
      (node (ref "R127") (pin "1") (pinfunction "1_1") (pintype "passive"))
      (node (ref "R83") (pin "1") (pinfunction "1_1") (pintype "passive"))
      (node (ref "U13") (pin "48") (pinfunction "DVDD_48") (pintype "passive"))
      (node (ref "U13") (pin "50") (pinfunction "DVDD_50") (pintype "passive"))
      (node (ref "U13") (pin "52") (pinfunction "CLKSEL_52") (pintype "passive"))
      (node (ref "U9") (pin "48") (pinfunction "DVDD_48") (pintype "passive"))
      (node (ref "U9") (pin "50") (pinfunction "DVDD_50") (pintype "passive"))
      (node (ref "U9") (pin "52") (pinfunction "CLKSEL_52") (pintype "passive"))
    )
    (net (code "88") (name "GND") (class "Default")
      (node (ref "C100") (pin "1") (pinfunction "1_1") (pintype "passive"))
      (node (ref "C101") (pin "1") (pinfunction "1_1") (pintype "passive"))
      (node (ref "C148") (pin "1") (pinfunction "1_1") (pintype "passive"))
      (node (ref "C149") (pin "1") (pinfunction "1_1") (pintype "passive"))
      (node (ref "C150") (pin "1") (pinfunction "1_1") (pintype "passive"))
      (node (ref "C38") (pin "1") (pinfunction "1_1") (pintype "passive"))
      (node (ref "C41") (pin "1") (pinfunction "1_1") (pintype "passive"))
      (node (ref "C95") (pin "1") (pinfunction "1_1") (pintype "passive"))
      (node (ref "C96") (pin "1") (pinfunction "1_1") (pintype "passive"))
      (node (ref "C97") (pin "1") (pinfunction "1_1") (pintype "passive"))
      (node (ref "P1") (pin "13") (pinfunction "13_13") (pintype "passive"))
      (node (ref "P1") (pin "8") (pinfunction "8_8") (pintype "passive"))
      (node (ref "R145") (pin "1") (pinfunction "1_1") (pintype "passive"))
      (node (ref "U13") (pin "33") (pinfunction "DGND_33") (pintype "passive"))
      (node (ref "U13") (pin "37") (pinfunction "CLK_37") (pintype "passive"))
      (node (ref "U13") (pin "38") (pinfunction "START_38") (pintype "passive"))
      (node (ref "U13") (pin "41") (pinfunction "DAISY_IN_41") (pintype "passive"))
      (node (ref "U13") (pin "49") (pinfunction "DGND_49") (pintype "passive"))
      (node (ref "U13") (pin "51") (pinfunction "DGND_51") (pintype "passive"))
      (node (ref "U9") (pin "33") (pinfunction "DGND_33") (pintype "passive"))
      (node (ref "U9") (pin "37") (pinfunction "CLK_37") (pintype "passive"))
      (node (ref "U9") (pin "38") (pinfunction "START_38") (pintype "passive"))
      (node (ref "U9") (pin "41") (pinfunction "DAISY_IN_41") (pintype "passive"))
      (node (ref "U9") (pin "49") (pinfunction "DGND_49") (pintype "passive"))
      (node (ref "U9") (pin "51") (pinfunction "DGND_51") (pintype "passive"))
    )
    (net (code "89") (name "Net-(C42-Pad2)") (class "Default")
      (node (ref "C42") (pin "2") (pinfunction "2_2") (pintype "passive"))
      (node (ref "DS2") (pin "1") (pinfunction "1_1") (pintype "passive"))
      (node (ref "R60") (pin "2") (pinfunction "2_2") (pintype "passive"))
      (node (ref "R61") (pin "1") (pinfunction "1_1") (pintype "passive"))
    )
    (net (code "90") (name "Net-(C44-Pad2)") (class "Default")
      (node (ref "C44") (pin "2") (pinfunction "2_2") (pintype "passive"))
      (node (ref "DS3") (pin "1") (pinfunction "1_1") (pintype "passive"))
      (node (ref "R62") (pin "2") (pinfunction "2_2") (pintype "passive"))
      (node (ref "R63") (pin "1") (pinfunction "1_1") (pintype "passive"))
    )
    (net (code "91") (name "Net-(C47-Pad2)") (class "Default")
      (node (ref "C47") (pin "2") (pinfunction "2_2") (pintype "passive"))
      (node (ref "DS4") (pin "1") (pinfunction "1_1") (pintype "passive"))
      (node (ref "R65") (pin "2") (pinfunction "2_2") (pintype "passive"))
      (node (ref "R66") (pin "1") (pinfunction "1_1") (pintype "passive"))
    )
    (net (code "92") (name "Net-(C49-Pad2)") (class "Default")
      (node (ref "C49") (pin "2") (pinfunction "2_2") (pintype "passive"))
      (node (ref "DS5") (pin "1") (pinfunction "1_1") (pintype "passive"))
      (node (ref "R67") (pin "2") (pinfunction "2_2") (pintype "passive"))
      (node (ref "R68") (pin "1") (pinfunction "1_1") (pintype "passive"))
    )
    (net (code "93") (name "Net-(C54-Pad2)") (class "Default")
      (node (ref "C54") (pin "2") (pinfunction "2_2") (pintype "passive"))
      (node (ref "DS6") (pin "1") (pinfunction "1_1") (pintype "passive"))
      (node (ref "R69") (pin "2") (pinfunction "2_2") (pintype "passive"))
      (node (ref "R70") (pin "1") (pinfunction "1_1") (pintype "passive"))
    )
    (net (code "94") (name "Net-(C59-Pad2)") (class "Default")
      (node (ref "C59") (pin "2") (pinfunction "2_2") (pintype "passive"))
      (node (ref "DS7") (pin "1") (pinfunction "1_1") (pintype "passive"))
      (node (ref "R72") (pin "2") (pinfunction "2_2") (pintype "passive"))
      (node (ref "R73") (pin "1") (pinfunction "1_1") (pintype "passive"))
    )
    (net (code "95") (name "Net-(C61-Pad2)") (class "Default")
      (node (ref "C61") (pin "2") (pinfunction "2_2") (pintype "passive"))
      (node (ref "DS8") (pin "1") (pinfunction "1_1") (pintype "passive"))
      (node (ref "R74") (pin "2") (pinfunction "2_2") (pintype "passive"))
      (node (ref "R75") (pin "1") (pinfunction "1_1") (pintype "passive"))
    )
    (net (code "96") (name "Net-(C63-Pad2)") (class "Default")
      (node (ref "C63") (pin "2") (pinfunction "2_2") (pintype "passive"))
      (node (ref "DS9") (pin "1") (pinfunction "1_1") (pintype "passive"))
      (node (ref "R77") (pin "2") (pinfunction "2_2") (pintype "passive"))
      (node (ref "R80") (pin "1") (pinfunction "1_1") (pintype "passive"))
    )
    (net (code "97") (name "Net-(C65-Pad2)") (class "Default")
      (node (ref "C65") (pin "2") (pinfunction "2_2") (pintype "passive"))
      (node (ref "DS10") (pin "1") (pinfunction "1_1") (pintype "passive"))
      (node (ref "R81") (pin "2") (pinfunction "2_2") (pintype "passive"))
      (node (ref "R82") (pin "1") (pinfunction "1_1") (pintype "passive"))
    )
    (net (code "98") (name "Net-(C67-Pad2)") (class "Default")
      (node (ref "C67") (pin "2") (pinfunction "2_2") (pintype "passive"))
      (node (ref "DS11") (pin "1") (pinfunction "1_1") (pintype "passive"))
      (node (ref "R84") (pin "2") (pinfunction "2_2") (pintype "passive"))
      (node (ref "R85") (pin "1") (pinfunction "1_1") (pintype "passive"))
    )
    (net (code "99") (name "Net-(C69-Pad2)") (class "Default")
      (node (ref "C69") (pin "2") (pinfunction "2_2") (pintype "passive"))
      (node (ref "DS12") (pin "1") (pinfunction "1_1") (pintype "passive"))
      (node (ref "R86") (pin "2") (pinfunction "2_2") (pintype "passive"))
      (node (ref "R87") (pin "1") (pinfunction "1_1") (pintype "passive"))
    )
    (net (code "100") (name "Net-(C72-Pad2)") (class "Default")
      (node (ref "C72") (pin "2") (pinfunction "2_2") (pintype "passive"))
      (node (ref "DS13") (pin "1") (pinfunction "1_1") (pintype "passive"))
      (node (ref "R88") (pin "2") (pinfunction "2_2") (pintype "passive"))
      (node (ref "R89") (pin "1") (pinfunction "1_1") (pintype "passive"))
    )
    (net (code "101") (name "Net-(C74-Pad2)") (class "Default")
      (node (ref "C74") (pin "2") (pinfunction "2_2") (pintype "passive"))
      (node (ref "DS14") (pin "1") (pinfunction "1_1") (pintype "passive"))
      (node (ref "R90") (pin "2") (pinfunction "2_2") (pintype "passive"))
      (node (ref "R91") (pin "1") (pinfunction "1_1") (pintype "passive"))
    )
    (net (code "102") (name "Net-(C82-Pad2)") (class "Default")
      (node (ref "C82") (pin "2") (pinfunction "2_2") (pintype "passive"))
      (node (ref "DS15") (pin "1") (pinfunction "1_1") (pintype "passive"))
      (node (ref "R93") (pin "2") (pinfunction "2_2") (pintype "passive"))
      (node (ref "R94") (pin "1") (pinfunction "1_1") (pintype "passive"))
    )
    (net (code "103") (name "Net-(C84-Pad2)") (class "Default")
      (node (ref "C84") (pin "2") (pinfunction "2_2") (pintype "passive"))
      (node (ref "DS16") (pin "1") (pinfunction "1_1") (pintype "passive"))
      (node (ref "R95") (pin "2") (pinfunction "2_2") (pintype "passive"))
      (node (ref "R96") (pin "1") (pinfunction "1_1") (pintype "passive"))
    )
    (net (code "104") (name "Net-(C86-Pad2)") (class "Default")
      (node (ref "C86") (pin "2") (pinfunction "2_2") (pintype "passive"))
      (node (ref "DS17") (pin "1") (pinfunction "1_1") (pintype "passive"))
      (node (ref "R97") (pin "2") (pinfunction "2_2") (pintype "passive"))
      (node (ref "R98") (pin "1") (pinfunction "1_1") (pintype "passive"))
    )
    (net (code "105") (name "Net-(C88-Pad2)") (class "Default")
      (node (ref "C88") (pin "2") (pinfunction "2_2") (pintype "passive"))
      (node (ref "DS18") (pin "1") (pinfunction "1_1") (pintype "passive"))
      (node (ref "R100") (pin "1") (pinfunction "1_1") (pintype "passive"))
      (node (ref "R99") (pin "2") (pinfunction "2_2") (pintype "passive"))
    )
    (net (code "106") (name "Net-(C102-Pad2)") (class "Default")
      (node (ref "C102") (pin "2") (pinfunction "2_2") (pintype "passive"))
      (node (ref "DS19") (pin "1") (pinfunction "1_1") (pintype "passive"))
      (node (ref "R106") (pin "2") (pinfunction "2_2") (pintype "passive"))
      (node (ref "R107") (pin "1") (pinfunction "1_1") (pintype "passive"))
    )
    (net (code "107") (name "Net-(C104-Pad2)") (class "Default")
      (node (ref "C104") (pin "2") (pinfunction "2_2") (pintype "passive"))
      (node (ref "DS20") (pin "1") (pinfunction "1_1") (pintype "passive"))
      (node (ref "R108") (pin "2") (pinfunction "2_2") (pintype "passive"))
      (node (ref "R109") (pin "1") (pinfunction "1_1") (pintype "passive"))
    )
    (net (code "108") (name "Net-(C106-Pad2)") (class "Default")
      (node (ref "C106") (pin "2") (pinfunction "2_2") (pintype "passive"))
      (node (ref "DS21") (pin "1") (pinfunction "1_1") (pintype "passive"))
      (node (ref "R111") (pin "2") (pinfunction "2_2") (pintype "passive"))
      (node (ref "R112") (pin "1") (pinfunction "1_1") (pintype "passive"))
    )
    (net (code "109") (name "Net-(C108-Pad2)") (class "Default")
      (node (ref "C108") (pin "2") (pinfunction "2_2") (pintype "passive"))
      (node (ref "DS22") (pin "1") (pinfunction "1_1") (pintype "passive"))
      (node (ref "R113") (pin "2") (pinfunction "2_2") (pintype "passive"))
      (node (ref "R114") (pin "1") (pinfunction "1_1") (pintype "passive"))
    )
    (net (code "110") (name "Net-(C110-Pad2)") (class "Default")
      (node (ref "C110") (pin "2") (pinfunction "2_2") (pintype "passive"))
      (node (ref "DS23") (pin "1") (pinfunction "1_1") (pintype "passive"))
      (node (ref "R115") (pin "2") (pinfunction "2_2") (pintype "passive"))
      (node (ref "R116") (pin "1") (pinfunction "1_1") (pintype "passive"))
    )
    (net (code "111") (name "Net-(C112-Pad2)") (class "Default")
      (node (ref "C112") (pin "2") (pinfunction "2_2") (pintype "passive"))
      (node (ref "DS24") (pin "1") (pinfunction "1_1") (pintype "passive"))
      (node (ref "R118") (pin "2") (pinfunction "2_2") (pintype "passive"))
      (node (ref "R119") (pin "1") (pinfunction "1_1") (pintype "passive"))
    )
    (net (code "112") (name "Net-(C114-Pad2)") (class "Default")
      (node (ref "C114") (pin "2") (pinfunction "2_2") (pintype "passive"))
      (node (ref "DS25") (pin "1") (pinfunction "1_1") (pintype "passive"))
      (node (ref "R120") (pin "2") (pinfunction "2_2") (pintype "passive"))
      (node (ref "R121") (pin "1") (pinfunction "1_1") (pintype "passive"))
    )
    (net (code "113") (name "Net-(C116-Pad2)") (class "Default")
      (node (ref "C116") (pin "2") (pinfunction "2_2") (pintype "passive"))
      (node (ref "DS26") (pin "1") (pinfunction "1_1") (pintype "passive"))
      (node (ref "R123") (pin "2") (pinfunction "2_2") (pintype "passive"))
      (node (ref "R124") (pin "1") (pinfunction "1_1") (pintype "passive"))
    )
    (net (code "114") (name "Net-(C118-Pad2)") (class "Default")
      (node (ref "C118") (pin "2") (pinfunction "2_2") (pintype "passive"))
      (node (ref "DS27") (pin "1") (pinfunction "1_1") (pintype "passive"))
      (node (ref "R125") (pin "2") (pinfunction "2_2") (pintype "passive"))
      (node (ref "R126") (pin "1") (pinfunction "1_1") (pintype "passive"))
    )
    (net (code "115") (name "Net-(C120-Pad2)") (class "Default")
      (node (ref "C120") (pin "2") (pinfunction "2_2") (pintype "passive"))
      (node (ref "DS28") (pin "1") (pinfunction "1_1") (pintype "passive"))
      (node (ref "R128") (pin "2") (pinfunction "2_2") (pintype "passive"))
      (node (ref "R129") (pin "1") (pinfunction "1_1") (pintype "passive"))
    )
    (net (code "116") (name "Net-(C122-Pad2)") (class "Default")
      (node (ref "C122") (pin "2") (pinfunction "2_2") (pintype "passive"))
      (node (ref "DS29") (pin "1") (pinfunction "1_1") (pintype "passive"))
      (node (ref "R130") (pin "2") (pinfunction "2_2") (pintype "passive"))
      (node (ref "R131") (pin "1") (pinfunction "1_1") (pintype "passive"))
    )
    (net (code "117") (name "Net-(C125-Pad2)") (class "Default")
      (node (ref "C125") (pin "2") (pinfunction "2_2") (pintype "passive"))
      (node (ref "DS30") (pin "1") (pinfunction "1_1") (pintype "passive"))
      (node (ref "R132") (pin "2") (pinfunction "2_2") (pintype "passive"))
      (node (ref "R133") (pin "1") (pinfunction "1_1") (pintype "passive"))
    )
    (net (code "118") (name "Net-(C127-Pad2)") (class "Default")
      (node (ref "C127") (pin "2") (pinfunction "2_2") (pintype "passive"))
      (node (ref "DS31") (pin "1") (pinfunction "1_1") (pintype "passive"))
      (node (ref "R134") (pin "2") (pinfunction "2_2") (pintype "passive"))
      (node (ref "R135") (pin "1") (pinfunction "1_1") (pintype "passive"))
    )
    (net (code "119") (name "Net-(C135-Pad2)") (class "Default")
      (node (ref "C135") (pin "2") (pinfunction "2_2") (pintype "passive"))
      (node (ref "DS32") (pin "1") (pinfunction "1_1") (pintype "passive"))
      (node (ref "R137") (pin "2") (pinfunction "2_2") (pintype "passive"))
      (node (ref "R138") (pin "1") (pinfunction "1_1") (pintype "passive"))
    )
    (net (code "120") (name "Net-(C137-Pad2)") (class "Default")
      (node (ref "C137") (pin "2") (pinfunction "2_2") (pintype "passive"))
      (node (ref "DS33") (pin "1") (pinfunction "1_1") (pintype "passive"))
      (node (ref "R139") (pin "2") (pinfunction "2_2") (pintype "passive"))
      (node (ref "R140") (pin "1") (pinfunction "1_1") (pintype "passive"))
    )
    (net (code "121") (name "Net-(C139-Pad2)") (class "Default")
      (node (ref "C139") (pin "2") (pinfunction "2_2") (pintype "passive"))
      (node (ref "DS34") (pin "1") (pinfunction "1_1") (pintype "passive"))
      (node (ref "R141") (pin "2") (pinfunction "2_2") (pintype "passive"))
      (node (ref "R142") (pin "1") (pinfunction "1_1") (pintype "passive"))
    )
    (net (code "122") (name "Net-(C141-Pad2)") (class "Default")
      (node (ref "C141") (pin "2") (pinfunction "2_2") (pintype "passive"))
      (node (ref "DS35") (pin "1") (pinfunction "1_1") (pintype "passive"))
      (node (ref "R143") (pin "2") (pinfunction "2_2") (pintype "passive"))
      (node (ref "R144") (pin "1") (pinfunction "1_1") (pintype "passive"))
    )
    (net (code "123") (name "Net-(P11-Pad1)") (class "Default")
      (node (ref "P11") (pin "1") (pinfunction "1_1") (pintype "passive"))
      (node (ref "R52") (pin "1") (pinfunction "1_1") (pintype "passive"))
    )
    (net (code "124") (name "Net-(P14-Pad1)") (class "Default")
      (node (ref "P14") (pin "1") (pinfunction "1_1") (pintype "passive"))
      (node (ref "P15") (pin "3") (pinfunction "3_3") (pintype "passive"))
    )
    (net (code "125") (name "Net-(P15-Pad2)") (class "Default")
      (node (ref "P15") (pin "2") (pinfunction "2_2") (pintype "passive"))
      (node (ref "R92") (pin "1") (pinfunction "1_1") (pintype "passive"))
    )
    (net (code "126") (name "Net-(P17-Pad1)") (class "Default")
      (node (ref "P17") (pin "1") (pinfunction "1_1") (pintype "passive"))
      (node (ref "R102") (pin "1") (pinfunction "1_1") (pintype "passive"))
    )
    (net (code "127") (name "Net-(P20-Pad1)") (class "Default")
      (node (ref "P20") (pin "1") (pinfunction "1_1") (pintype "passive"))
      (node (ref "P21") (pin "3") (pinfunction "3_3") (pintype "passive"))
    )
    (net (code "128") (name "Net-(P21-Pad2)") (class "Default")
      (node (ref "P21") (pin "2") (pinfunction "2_2") (pintype "passive"))
      (node (ref "R136") (pin "1") (pinfunction "1_1") (pintype "passive"))
    )
    (net (code "129") (name "Net-(TVS5-B)") (class "Default")
      (node (ref "C48") (pin "2") (pinfunction "2_2") (pintype "passive"))
      (node (ref "P11") (pin "2") (pinfunction "2_2") (pintype "passive"))
      (node (ref "R64") (pin "2") (pinfunction "2_2") (pintype "passive"))
      (node (ref "R66") (pin "2") (pinfunction "2_2") (pintype "passive"))
      (node (ref "TVS5") (pin "2") (pinfunction "B_2") (pintype "passive"))
    )
    (net (code "130") (name "Net-(TVS22-B)") (class "Default")
      (node (ref "C107") (pin "2") (pinfunction "2_2") (pintype "passive"))
      (node (ref "P17") (pin "2") (pinfunction "2_2") (pintype "passive"))
      (node (ref "R110") (pin "2") (pinfunction "2_2") (pintype "passive"))
      (node (ref "R112") (pin "2") (pinfunction "2_2") (pintype "passive"))
      (node (ref "TVS22") (pin "2") (pinfunction "B_2") (pintype "passive"))
    )
    (net (code "131") (name "Net-(U8A-IN1+)") (class "Default")
      (node (ref "R52") (pin "2") (pinfunction "2_2") (pintype "passive"))
      (node (ref "U8") (pin "3") (pinfunction "IN1+_3") (pintype "input"))
    )
    (net (code "132") (name "Net-(U8B-IN2+)") (class "Default")
      (node (ref "R71") (pin "2") (pinfunction "2_2") (pintype "passive"))
      (node (ref "R76") (pin "1") (pinfunction "1_1") (pintype "passive"))
      (node (ref "U8") (pin "5") (pinfunction "IN2+_5") (pintype "input"))
    )
    (net (code "133") (name "Net-(U8B-IN2-)") (class "Default")
      (node (ref "P13") (pin "2") (pinfunction "2_2") (pintype "passive"))
      (node (ref "U8") (pin "6") (pinfunction "IN2-_6") (pintype "input"))
      (node (ref "U8") (pin "7") (pinfunction "OUT2_7") (pintype "output"))
    )
    (net (code "134") (name "Net-(U9-BIASIN)") (class "Default")
      (node (ref "P12") (pin "3") (pinfunction "3_3") (pintype "passive"))
      (node (ref "P13") (pin "3") (pinfunction "3_3") (pintype "passive"))
      (node (ref "U9") (pin "62") (pinfunction "BIASIN_62") (pintype "passive"))
    )
    (net (code "135") (name "Net-(U9-BIASINV)") (class "Default")
      (node (ref "C37") (pin "1") (pinfunction "1_1") (pintype "passive"))
      (node (ref "R55") (pin "1") (pinfunction "1_1") (pintype "passive"))
      (node (ref "U9") (pin "61") (pinfunction "BIASINV_61") (pintype "passive"))
    )
    (net (code "136") (name "Net-(U9-BIASOUT)") (class "Default")
      (node (ref "C37") (pin "2") (pinfunction "2_2") (pintype "passive"))
      (node (ref "P12") (pin "2") (pinfunction "2_2") (pintype "passive"))
      (node (ref "R55") (pin "2") (pinfunction "2_2") (pintype "passive"))
      (node (ref "R64") (pin "1") (pinfunction "1_1") (pintype "passive"))
      (node (ref "U9") (pin "63") (pinfunction "BIASOUT_63") (pintype "passive"))
    )
    (net (code "137") (name "Net-(U9-BIASREF)") (class "Default")
      (node (ref "R53") (pin "2") (pinfunction "2_2") (pintype "passive"))
      (node (ref "R54") (pin "2") (pinfunction "2_2") (pintype "passive"))
      (node (ref "R54") (pin "3") (pinfunction "3_3") (pintype "passive"))
      (node (ref "U9") (pin "60") (pinfunction "BIASREF_60") (pintype "passive"))
    )
    (net (code "138") (name "Net-(U9-SRB1)") (class "Default")
      (node (ref "P14") (pin "2") (pinfunction "2_2") (pintype "passive"))
      (node (ref "U9") (pin "17") (pinfunction "SRB1_17") (pintype "passive"))
    )
    (net (code "139") (name "Net-(U9-SRB2)") (class "Default")
      (node (ref "P15") (pin "1") (pinfunction "1_1") (pintype "passive"))
      (node (ref "U9") (pin "18") (pinfunction "SRB2_18") (pintype "passive"))
    )
    (net (code "140") (name "Net-(U9-VCAP1)") (class "Default")
      (node (ref "C79") (pin "2") (pinfunction "2_2") (pintype "passive"))
      (node (ref "C80") (pin "2") (pinfunction "2_2") (pintype "passive"))
      (node (ref "U9") (pin "28") (pinfunction "VCAP1_28") (pintype "passive"))
    )
    (net (code "141") (name "Net-(U9-VCAP2)") (class "Default")
      (node (ref "C81") (pin "2") (pinfunction "2_2") (pintype "passive"))
      (node (ref "U9") (pin "30") (pinfunction "VCAP2_30") (pintype "passive"))
    )
    (net (code "142") (name "Net-(U9-VCAP3)") (class "Default")
      (node (ref "C38") (pin "2") (pinfunction "2_2") (pintype "passive"))
      (node (ref "C41") (pin "2") (pinfunction "2_2") (pintype "passive"))
      (node (ref "U9") (pin "55") (pinfunction "VCAP3_55") (pintype "passive"))
    )
    (net (code "143") (name "Net-(U9-VCAP4)") (class "Default")
      (node (ref "C78") (pin "2") (pinfunction "2_2") (pintype "passive"))
      (node (ref "U9") (pin "26") (pinfunction "VCAP4_26") (pintype "passive"))
    )
    (net (code "144") (name "Net-(U9-VREFP)") (class "Default")
      (node (ref "C76") (pin "2") (pinfunction "2_2") (pintype "passive"))
      (node (ref "C77") (pin "2") (pinfunction "2_2") (pintype "passive"))
      (node (ref "U9") (pin "24") (pinfunction "VREFP_24") (pintype "passive"))
    )
    (net (code "145") (name "Net-(U9-~{PWDN})") (class "Default")
      (node (ref "R83") (pin "2") (pinfunction "2_2") (pintype "passive"))
      (node (ref "U9") (pin "35") (pinfunction "~{PWDN}_35") (pintype "passive"))
      (node (ref "U9") (pin "36") (pinfunction "~{RESET}_36") (pintype "passive"))
    )
    (net (code "146") (name "Net-(U11A-IN1+)") (class "Default")
      (node (ref "R92") (pin "2") (pinfunction "2_2") (pintype "passive"))
      (node (ref "U11") (pin "3") (pinfunction "IN1+_3") (pintype "input"))
    )
    (net (code "147") (name "Net-(U11A-IN1-)") (class "Default")
      (node (ref "P14") (pin "3") (pinfunction "3_3") (pintype "passive"))
      (node (ref "U11") (pin "1") (pinfunction "OUT1_1") (pintype "output"))
      (node (ref "U11") (pin "2") (pinfunction "IN1-_2") (pintype "input"))
    )
    (net (code "148") (name "Net-(U11B-IN2+)") (class "Default")
      (node (ref "R117") (pin "2") (pinfunction "2_2") (pintype "passive"))
      (node (ref "R122") (pin "1") (pinfunction "1_1") (pintype "passive"))
      (node (ref "U11") (pin "5") (pinfunction "IN2+_5") (pintype "input"))
    )
    (net (code "149") (name "Net-(U11B-IN2-)") (class "Default")
      (node (ref "P19") (pin "2") (pinfunction "2_2") (pintype "passive"))
      (node (ref "U11") (pin "6") (pinfunction "IN2-_6") (pintype "input"))
      (node (ref "U11") (pin "7") (pinfunction "OUT2_7") (pintype "output"))
    )
    (net (code "150") (name "Net-(U12A-IN1+)") (class "Default")
      (node (ref "R102") (pin "2") (pinfunction "2_2") (pintype "passive"))
      (node (ref "U12") (pin "3") (pinfunction "IN1+_3") (pintype "input"))
    )
    (net (code "151") (name "Net-(U13-BIASIN)") (class "Default")
      (node (ref "P18") (pin "3") (pinfunction "3_3") (pintype "passive"))
      (node (ref "P19") (pin "3") (pinfunction "3_3") (pintype "passive"))
      (node (ref "U13") (pin "62") (pinfunction "BIASIN_62") (pintype "passive"))
    )
    (net (code "152") (name "Net-(U13-BIASINV)") (class "Default")
      (node (ref "C99") (pin "1") (pinfunction "1_1") (pintype "passive"))
      (node (ref "R105") (pin "1") (pinfunction "1_1") (pintype "passive"))
      (node (ref "U13") (pin "61") (pinfunction "BIASINV_61") (pintype "passive"))
    )
    (net (code "153") (name "Net-(U13-BIASOUT)") (class "Default")
      (node (ref "C99") (pin "2") (pinfunction "2_2") (pintype "passive"))
      (node (ref "P18") (pin "2") (pinfunction "2_2") (pintype "passive"))
      (node (ref "R105") (pin "2") (pinfunction "2_2") (pintype "passive"))
      (node (ref "R110") (pin "1") (pinfunction "1_1") (pintype "passive"))
      (node (ref "U13") (pin "63") (pinfunction "BIASOUT_63") (pintype "passive"))
    )
    (net (code "154") (name "Net-(U13-BIASREF)") (class "Default")
      (node (ref "R103") (pin "2") (pinfunction "2_2") (pintype "passive"))
      (node (ref "R104") (pin "2") (pinfunction "2_2") (pintype "passive"))
      (node (ref "R104") (pin "3") (pinfunction "3_3") (pintype "passive"))
      (node (ref "U13") (pin "60") (pinfunction "BIASREF_60") (pintype "passive"))
    )
    (net (code "155") (name "Net-(U13-SRB1)") (class "Default")
      (node (ref "P20") (pin "2") (pinfunction "2_2") (pintype "passive"))
      (node (ref "U13") (pin "17") (pinfunction "SRB1_17") (pintype "passive"))
    )
    (net (code "156") (name "Net-(U13-SRB2)") (class "Default")
      (node (ref "P21") (pin "1") (pinfunction "1_1") (pintype "passive"))
      (node (ref "U13") (pin "18") (pinfunction "SRB2_18") (pintype "passive"))
    )
    (net (code "157") (name "Net-(U13-VCAP1)") (class "Default")
      (node (ref "C132") (pin "2") (pinfunction "2_2") (pintype "passive"))
      (node (ref "C133") (pin "2") (pinfunction "2_2") (pintype "passive"))
      (node (ref "U13") (pin "28") (pinfunction "VCAP1_28") (pintype "passive"))
    )
    (net (code "158") (name "Net-(U13-VCAP2)") (class "Default")
      (node (ref "C134") (pin "2") (pinfunction "2_2") (pintype "passive"))
      (node (ref "U13") (pin "30") (pinfunction "VCAP2_30") (pintype "passive"))
    )
    (net (code "159") (name "Net-(U13-VCAP3)") (class "Default")
      (node (ref "C100") (pin "2") (pinfunction "2_2") (pintype "passive"))
      (node (ref "C101") (pin "2") (pinfunction "2_2") (pintype "passive"))
      (node (ref "U13") (pin "55") (pinfunction "VCAP3_55") (pintype "passive"))
    )
    (net (code "160") (name "Net-(U13-VCAP4)") (class "Default")
      (node (ref "C131") (pin "2") (pinfunction "2_2") (pintype "passive"))
      (node (ref "U13") (pin "26") (pinfunction "VCAP4_26") (pintype "passive"))
    )
    (net (code "161") (name "Net-(U13-VREFP)") (class "Default")
      (node (ref "C129") (pin "2") (pinfunction "2_2") (pintype "passive"))
      (node (ref "C130") (pin "2") (pinfunction "2_2") (pintype "passive"))
      (node (ref "U13") (pin "24") (pinfunction "VREFP_24") (pintype "passive"))
    )
    (net (code "162") (name "Net-(U13-~{PWDN})") (class "Default")
      (node (ref "R127") (pin "2") (pinfunction "2_2") (pintype "passive"))
      (node (ref "U13") (pin "35") (pinfunction "~{PWDN}_35") (pintype "passive"))
      (node (ref "U13") (pin "36") (pinfunction "~{RESET}_36") (pintype "passive"))
    )
    (net (code "163") (name "Net-(U14A-IN1+)") (class "Default")
      (node (ref "R136") (pin "2") (pinfunction "2_2") (pintype "passive"))
      (node (ref "U14") (pin "3") (pinfunction "IN1+_3") (pintype "input"))
    )
    (net (code "164") (name "Net-(U14A-IN1-)") (class "Default")
      (node (ref "P20") (pin "3") (pinfunction "3_3") (pintype "passive"))
      (node (ref "U14") (pin "1") (pinfunction "OUT1_1") (pintype "output"))
      (node (ref "U14") (pin "2") (pinfunction "IN1-_2") (pintype "input"))
    )
    (net (code "165") (name "VDD5V_OUT") (class "Default")
      (node (ref "P1") (pin "14") (pinfunction "14_14") (pintype "passive"))
    )
    (net (code "166") (name "unconnected-(U9-GPIO1-Pad42)") (class "Default")
      (node (ref "U9") (pin "42") (pinfunction "GPIO1_42") (pintype "passive"))
    )
    (net (code "167") (name "unconnected-(U9-GPIO2-Pad44)") (class "Default")
      (node (ref "U9") (pin "44") (pinfunction "GPIO2_44") (pintype "passive"))
    )
    (net (code "168") (name "unconnected-(U9-GPIO3-Pad45)") (class "Default")
      (node (ref "U9") (pin "45") (pinfunction "GPIO3_45") (pintype "passive"))
    )
    (net (code "169") (name "unconnected-(U9-GPIO4-Pad46)") (class "Default")
      (node (ref "U9") (pin "46") (pinfunction "GPIO4_46") (pintype "passive"))
    )
    (net (code "170") (name "unconnected-(U9-NC-Pad27)") (class "Default")
      (node (ref "U9") (pin "27") (pinfunction "NC_27") (pintype "passive"))
    )
    (net (code "171") (name "unconnected-(U9-NC-Pad29)") (class "Default")
      (node (ref "U9") (pin "29") (pinfunction "NC_29") (pintype "passive"))
    )
    (net (code "172") (name "unconnected-(U9-RESERVED-Pad64)") (class "Default")
      (node (ref "U9") (pin "64") (pinfunction "RESERVED_64") (pintype "passive"))
    )
    (net (code "173") (name "unconnected-(U13-GPIO1-Pad42)") (class "Default")
      (node (ref "U13") (pin "42") (pinfunction "GPIO1_42") (pintype "passive"))
    )
    (net (code "174") (name "unconnected-(U13-GPIO2-Pad44)") (class "Default")
      (node (ref "U13") (pin "44") (pinfunction "GPIO2_44") (pintype "passive"))
    )
    (net (code "175") (name "unconnected-(U13-GPIO3-Pad45)") (class "Default")
      (node (ref "U13") (pin "45") (pinfunction "GPIO3_45") (pintype "passive"))
    )
    (net (code "176") (name "unconnected-(U13-GPIO4-Pad46)") (class "Default")
      (node (ref "U13") (pin "46") (pinfunction "GPIO4_46") (pintype "passive"))
    )
    (net (code "177") (name "unconnected-(U13-NC-Pad27)") (class "Default")
      (node (ref "U13") (pin "27") (pinfunction "NC_27") (pintype "passive"))
    )
    (net (code "178") (name "unconnected-(U13-NC-Pad29)") (class "Default")
      (node (ref "U13") (pin "29") (pinfunction "NC_29") (pintype "passive"))
    )
    (net (code "179") (name "unconnected-(U13-RESERVED-Pad64)") (class "Default")
      (node (ref "U13") (pin "64") (pinfunction "RESERVED_64") (pintype "passive"))
    )
  )
)
